# PA_Receiver.net
KiCad netlist of a schematic drawn in Altium Designer
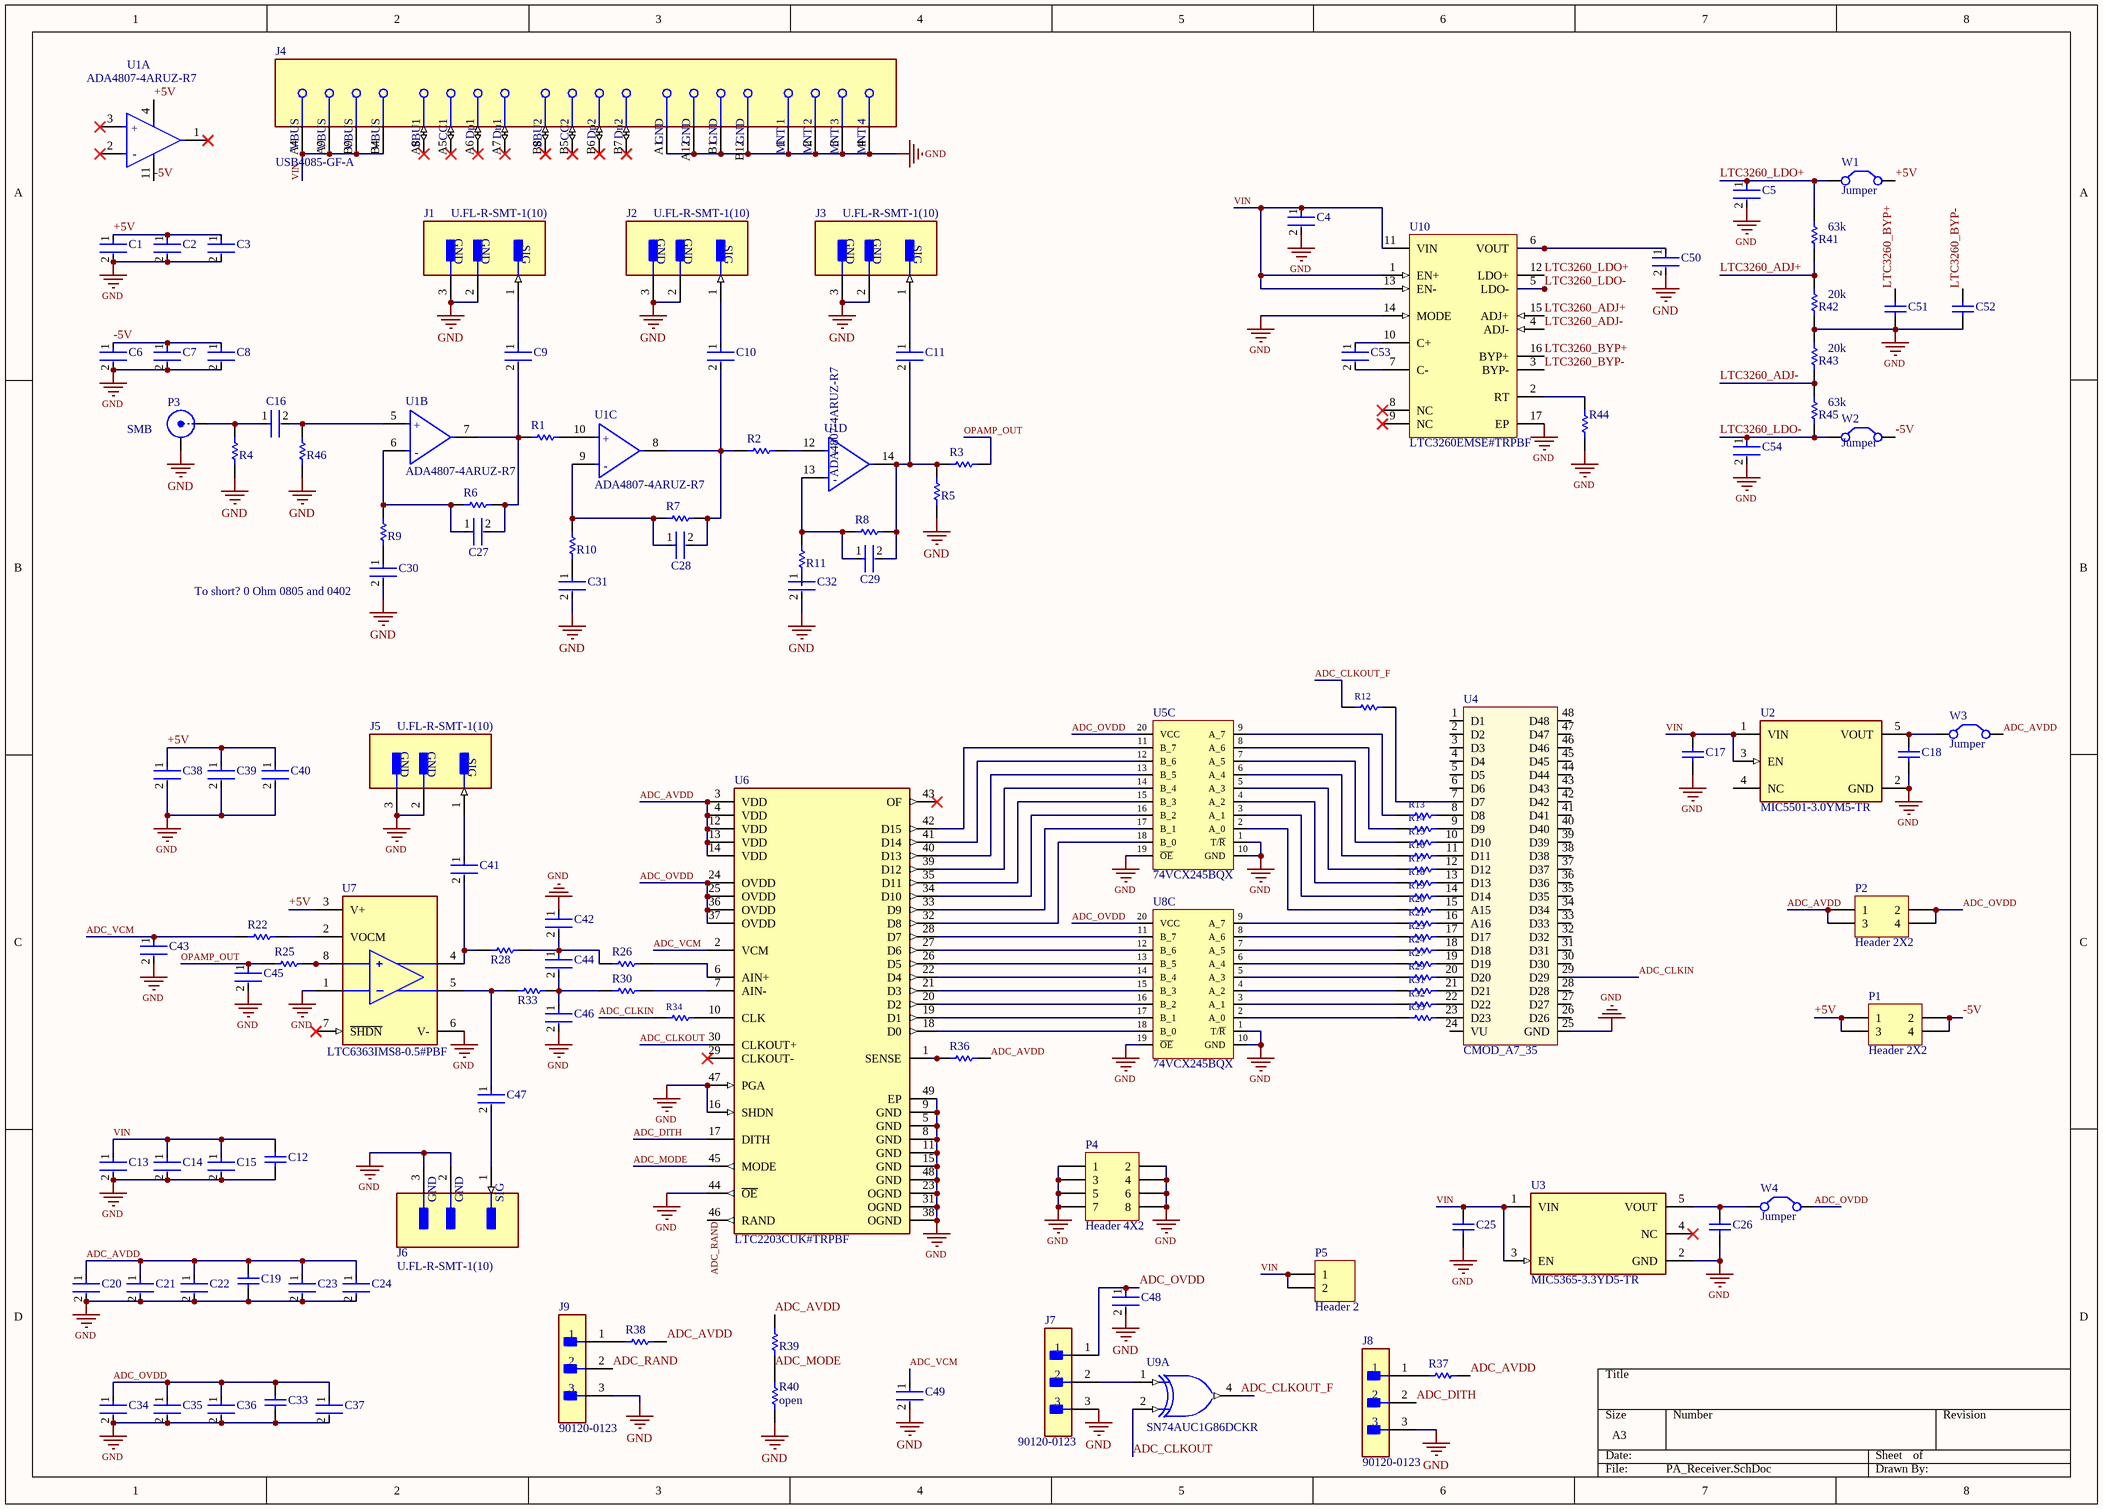
[diagram p0: PA_Receiver.SchDoc]

(export (version "E")
  (design (tool "Eeschema 10.0.6"))
  (components
    (comp (ref "C1")
      (value "CL21B106KOQNNNG")
      (footprint "FP-CL21B106KOQNNNG-MFG")
      (description "CAP CER 10UF 16V X7R 0805")
      (fields
        (field (name "TOLERANCE") "10%")
        (field (name "OCTOPART") "https://octopart.com/cl21b106koqnnng-samsung-19995691")
      )
      (libsource (lib "Altium Content Vault") (part "b4654b650e69147ec39a6b967a45e02"))
    )
    (comp (ref "C2")
      (value "GRM21BR71C475KE51K")
      (footprint "FP-GRM21B-0_15-MFG")
      (description "Chip Multilayer Ceramic Capacitors for General Purpose, 0805, 4.7uF, X7R, 15%, 10%, 16V")
      (fields (field (name "TOLERANCE") "10%"))
      (libsource (lib "Altium Content Vault") (part "b4654b650e69147ec39a6b967a45e02"))
    )
    (comp (ref "C3")
      (value "C0805C104K5RACTU")
      (footprint "FP-C0805C-DN-MFG")
      (description "CAP CER 0.1UF 50V X7R 0805")
      (fields
        (field (name "MANUFACTURER") "KEMET")
        (field (name "OCTOPART") "https://octopart.com/c0805c104k5ractu-kemet-143926")
      )
      (libsource (lib "Altium Content Vault") (part "b4654b650e69147ec39a6b967a45e02"))
    )
    (comp (ref "C4")
      (value "CL21B106KOQNNNG")
      (footprint "FP-CL21B106KOQNNNG-MFG")
      (description "CAP CER 10UF 16V X7R 0805")
      (fields
        (field (name "TOLERANCE") "10%")
        (field (name "OCTOPART") "https://octopart.com/cl21b106koqnnng-samsung-19995691")
      )
      (libsource (lib "Altium Content Vault") (part "b4654b650e69147ec39a6b967a45e02"))
    )
    (comp (ref "C5")
      (value "CL21B106KOQNNNG")
      (footprint "FP-CL21B106KOQNNNG-MFG")
      (description "CAP CER 10UF 16V X7R 0805")
      (fields
        (field (name "TOLERANCE") "10%")
        (field (name "OCTOPART") "https://octopart.com/cl21b106koqnnng-samsung-19995691")
      )
      (libsource (lib "Altium Content Vault") (part "b4654b650e69147ec39a6b967a45e02"))
    )
    (comp (ref "C6")
      (value "CL21B106KOQNNNG")
      (footprint "FP-CL21B106KOQNNNG-MFG")
      (description "CAP CER 10UF 16V X7R 0805")
      (fields
        (field (name "TOLERANCE") "10%")
        (field (name "OCTOPART") "https://octopart.com/cl21b106koqnnng-samsung-19995691")
      )
      (libsource (lib "Altium Content Vault") (part "b4654b650e69147ec39a6b967a45e02"))
    )
    (comp (ref "C7")
      (value "GRM21BR71C475KE51K")
      (footprint "FP-GRM21B-0_15-MFG")
      (description "Chip Multilayer Ceramic Capacitors for General Purpose, 0805, 4.7uF, X7R, 15%, 10%, 16V")
      (fields (field (name "TOLERANCE") "10%"))
      (libsource (lib "Altium Content Vault") (part "b4654b650e69147ec39a6b967a45e02"))
    )
    (comp (ref "C8")
      (value "C0805C104K5RACTU")
      (footprint "FP-C0805C-DN-MFG")
      (description "CAP CER 0.1UF 50V X7R 0805")
      (fields
        (field (name "MANUFACTURER") "KEMET")
        (field (name "OCTOPART") "https://octopart.com/c0805c104k5ractu-kemet-143926")
      )
      (libsource (lib "Altium Content Vault") (part "b4654b650e69147ec39a6b967a45e02"))
    )
    (comp (ref "C9")
      (value "C0805C102K5RACTU")
      (footprint "FP-C0805C-DN-MFG")
      (description "CAP CER 1000PF 50V X7R 0805")
      (fields
        (field (name "OCTOPART") "https://octopart.com/c0805c102k5ractu-kemet-93010")
        (field (name "TOLERANCE") "0.1")
      )
      (libsource (lib "Altium Content Vault") (part "b4654b650e69147ec39a6b967a45e02"))
    )
    (comp (ref "C10")
      (value "C0805C102K5RACTU")
      (footprint "FP-C0805C-DN-MFG")
      (description "CAP CER 1000PF 50V X7R 0805")
      (fields
        (field (name "OCTOPART") "https://octopart.com/c0805c102k5ractu-kemet-93010")
        (field (name "TOLERANCE") "0.1")
      )
      (libsource (lib "Altium Content Vault") (part "b4654b650e69147ec39a6b967a45e02"))
    )
    (comp (ref "C11")
      (value "C0805C102K5RACTU")
      (footprint "FP-C0805C-DN-MFG")
      (description "CAP CER 1000PF 50V X7R 0805")
      (fields
        (field (name "OCTOPART") "https://octopart.com/c0805c102k5ractu-kemet-93010")
        (field (name "TOLERANCE") "0.1")
      )
      (libsource (lib "Altium Content Vault") (part "b4654b650e69147ec39a6b967a45e02"))
    )
    (comp (ref "C12")
      (value "C0805C105K3RACTU")
      (footprint "CAPC2013X140X50LL20T25")
      (fields (field (name "MANUFACTURER") "Kemet"))
      (libsource (lib "Altium Content Vault") (part "CAP"))
    )
    (comp (ref "C13")
      (value "CL21B106KOQNNNG")
      (footprint "FP-CL21B106KOQNNNG-MFG")
      (description "CAP CER 10UF 16V X7R 0805")
      (fields
        (field (name "TOLERANCE") "10%")
        (field (name "OCTOPART") "https://octopart.com/cl21b106koqnnng-samsung-19995691")
      )
      (libsource (lib "Altium Content Vault") (part "b4654b650e69147ec39a6b967a45e02"))
    )
    (comp (ref "C14")
      (value "GRM21BR71C475KE51K")
      (footprint "FP-GRM21B-0_15-MFG")
      (description "Chip Multilayer Ceramic Capacitors for General Purpose, 0805, 4.7uF, X7R, 15%, 10%, 16V")
      (fields (field (name "TOLERANCE") "10%"))
      (libsource (lib "Altium Content Vault") (part "b4654b650e69147ec39a6b967a45e02"))
    )
    (comp (ref "C15")
      (value "C0805C104K5RACTU")
      (footprint "FP-C0805C-DN-MFG")
      (description "CAP CER 0.1UF 50V X7R 0805")
      (fields
        (field (name "MANUFACTURER") "KEMET")
        (field (name "OCTOPART") "https://octopart.com/c0805c104k5ractu-kemet-143926")
      )
      (libsource (lib "Altium Content Vault") (part "b4654b650e69147ec39a6b967a45e02"))
    )
    (comp (ref "C16")
      (value "CL21B222JBANNNC")
      (footprint "FP-CL21-IPC_B")
      (description "CL21 Series 0805 2.2nF 50V ±5% Tolerance X7R Multilayer Ceramic Chip Capacitor")
      (fields (field (name "TOLERANCE") "5%") (field (name "VOLTAGE") "50V"))
      (libsource (lib "Altium Content Vault") (part "b4654b650e69147ec39a6b967a45e02"))
    )
    (comp (ref "C17")
      (value "C0805C105K3RACTU")
      (footprint "CAPC2013X140X50LL20T25")
      (fields (field (name "MANUFACTURER") "Kemet"))
      (libsource (lib "Altium Content Vault") (part "CAP"))
    )
    (comp (ref "C18")
      (value "C0805C105K3RACTU")
      (footprint "CAPC2013X140X50LL20T25")
      (fields (field (name "MANUFACTURER") "Kemet"))
      (libsource (lib "Altium Content Vault") (part "CAP"))
    )
    (comp (ref "C19")
      (value "C0805C105K3RACTU")
      (footprint "CAPC2013X140X50LL20T25")
      (fields (field (name "MANUFACTURER") "Kemet"))
      (libsource (lib "Altium Content Vault") (part "CAP"))
    )
    (comp (ref "C20")
      (value "CL21B106KOQNNNG")
      (footprint "FP-CL21B106KOQNNNG-MFG")
      (description "CAP CER 10UF 16V X7R 0805")
      (fields
        (field (name "TOLERANCE") "10%")
        (field (name "OCTOPART") "https://octopart.com/cl21b106koqnnng-samsung-19995691")
      )
      (libsource (lib "Altium Content Vault") (part "b4654b650e69147ec39a6b967a45e02"))
    )
    (comp (ref "C21")
      (value "GRM21BR71C475KE51K")
      (footprint "FP-GRM21B-0_15-MFG")
      (description "Chip Multilayer Ceramic Capacitors for General Purpose, 0805, 4.7uF, X7R, 15%, 10%, 16V")
      (fields (field (name "TOLERANCE") "10%"))
      (libsource (lib "Altium Content Vault") (part "b4654b650e69147ec39a6b967a45e02"))
    )
    (comp (ref "C22")
      (value "C0805C104K5RACTU")
      (footprint "FP-C0805C-DN-MFG")
      (description "CAP CER 0.1UF 50V X7R 0805")
      (fields
        (field (name "MANUFACTURER") "KEMET")
        (field (name "OCTOPART") "https://octopart.com/c0805c104k5ractu-kemet-143926")
      )
      (libsource (lib "Altium Content Vault") (part "b4654b650e69147ec39a6b967a45e02"))
    )
    (comp (ref "C23")
      (value "C0805C104K5RACTU")
      (footprint "FP-C0805C-DN-MFG")
      (description "CAP CER 0.1UF 50V X7R 0805")
      (fields
        (field (name "MANUFACTURER") "KEMET")
        (field (name "OCTOPART") "https://octopart.com/c0805c104k5ractu-kemet-143926")
      )
      (libsource (lib "Altium Content Vault") (part "b4654b650e69147ec39a6b967a45e02"))
    )
    (comp (ref "C24")
      (value "C0805C104K5RACTU")
      (footprint "FP-C0805C-DN-MFG")
      (description "CAP CER 0.1UF 50V X7R 0805")
      (fields
        (field (name "MANUFACTURER") "KEMET")
        (field (name "OCTOPART") "https://octopart.com/c0805c104k5ractu-kemet-143926")
      )
      (libsource (lib "Altium Content Vault") (part "b4654b650e69147ec39a6b967a45e02"))
    )
    (comp (ref "C25")
      (value "C0805C105K3RACTU")
      (footprint "CAPC2013X140X50LL20T25")
      (fields (field (name "MANUFACTURER") "Kemet"))
      (libsource (lib "Altium Content Vault") (part "CAP"))
    )
    (comp (ref "C26")
      (value "C0805C105K3RACTU")
      (footprint "CAPC2013X140X50LL20T25")
      (fields (field (name "MANUFACTURER") "Kemet"))
      (libsource (lib "Altium Content Vault") (part "CAP"))
    )
    (comp (ref "C27")
      (value "C0805C150K5RACTU")
      (footprint "FP-C0805C-DN-MFG")
      (description "CAP CER SMD 0805 15PF 50V 10% X7")
      (fields
        (field (name "OCTOPART") "https://octopart.com/c0805c150k5ractu-kemet-88373275")
        (field (name "MANUFACTURER") "KEMET")
      )
      (libsource (lib "Altium Content Vault") (part "b4654b650e69147ec39a6b967a45e02"))
    )
    (comp (ref "C28")
      (value "C0805C150K5RACTU")
      (footprint "FP-C0805C-DN-MFG")
      (description "CAP CER SMD 0805 15PF 50V 10% X7")
      (fields
        (field (name "OCTOPART") "https://octopart.com/c0805c150k5ractu-kemet-88373275")
        (field (name "MANUFACTURER") "KEMET")
      )
      (libsource (lib "Altium Content Vault") (part "b4654b650e69147ec39a6b967a45e02"))
    )
    (comp (ref "C29")
      (value "C0805C150K5RACTU")
      (footprint "FP-C0805C-DN-MFG")
      (description "CAP CER SMD 0805 15PF 50V 10% X7")
      (fields
        (field (name "OCTOPART") "https://octopart.com/c0805c150k5ractu-kemet-88373275")
        (field (name "MANUFACTURER") "KEMET")
      )
      (libsource (lib "Altium Content Vault") (part "b4654b650e69147ec39a6b967a45e02"))
    )
    (comp (ref "C30")
      (value "CL21B106KOQNNNG")
      (footprint "FP-CL21B106KOQNNNG-MFG")
      (description "CAP CER 10UF 16V X7R 0805")
      (fields
        (field (name "TOLERANCE") "10%")
        (field (name "OCTOPART") "https://octopart.com/cl21b106koqnnng-samsung-19995691")
      )
      (libsource (lib "Altium Content Vault") (part "b4654b650e69147ec39a6b967a45e02"))
    )
    (comp (ref "C31")
      (value "CL21B106KOQNNNG")
      (footprint "FP-CL21B106KOQNNNG-MFG")
      (description "CAP CER 10UF 16V X7R 0805")
      (fields
        (field (name "TOLERANCE") "10%")
        (field (name "OCTOPART") "https://octopart.com/cl21b106koqnnng-samsung-19995691")
      )
      (libsource (lib "Altium Content Vault") (part "b4654b650e69147ec39a6b967a45e02"))
    )
    (comp (ref "C32")
      (value "CL21B106KOQNNNG")
      (footprint "FP-CL21B106KOQNNNG-MFG")
      (description "CAP CER 10UF 16V X7R 0805")
      (fields
        (field (name "TOLERANCE") "10%")
        (field (name "OCTOPART") "https://octopart.com/cl21b106koqnnng-samsung-19995691")
      )
      (libsource (lib "Altium Content Vault") (part "b4654b650e69147ec39a6b967a45e02"))
    )
    (comp (ref "C33")
      (value "C0805C105K3RACTU")
      (footprint "CAPC2013X140X50LL20T25")
      (fields (field (name "MANUFACTURER") "Kemet"))
      (libsource (lib "Altium Content Vault") (part "CAP"))
    )
    (comp (ref "C34")
      (value "CL21B106KOQNNNG")
      (footprint "FP-CL21B106KOQNNNG-MFG")
      (description "CAP CER 10UF 16V X7R 0805")
      (fields
        (field (name "TOLERANCE") "10%")
        (field (name "OCTOPART") "https://octopart.com/cl21b106koqnnng-samsung-19995691")
      )
      (libsource (lib "Altium Content Vault") (part "b4654b650e69147ec39a6b967a45e02"))
    )
    (comp (ref "C35")
      (value "GRM21BR71C475KE51K")
      (footprint "FP-GRM21B-0_15-MFG")
      (description "Chip Multilayer Ceramic Capacitors for General Purpose, 0805, 4.7uF, X7R, 15%, 10%, 16V")
      (fields (field (name "TOLERANCE") "10%"))
      (libsource (lib "Altium Content Vault") (part "b4654b650e69147ec39a6b967a45e02"))
    )
    (comp (ref "C36")
      (value "C0805C104K5RACTU")
      (footprint "FP-C0805C-DN-MFG")
      (description "CAP CER 0.1UF 50V X7R 0805")
      (fields
        (field (name "MANUFACTURER") "KEMET")
        (field (name "OCTOPART") "https://octopart.com/c0805c104k5ractu-kemet-143926")
      )
      (libsource (lib "Altium Content Vault") (part "b4654b650e69147ec39a6b967a45e02"))
    )
    (comp (ref "C37")
      (value "C0805C104K5RACTU")
      (footprint "FP-C0805C-DN-MFG")
      (description "CAP CER 0.1UF 50V X7R 0805")
      (fields
        (field (name "MANUFACTURER") "KEMET")
        (field (name "OCTOPART") "https://octopart.com/c0805c104k5ractu-kemet-143926")
      )
      (libsource (lib "Altium Content Vault") (part "b4654b650e69147ec39a6b967a45e02"))
    )
    (comp (ref "C38")
      (value "CL21B106KOQNNNG")
      (footprint "FP-CL21B106KOQNNNG-MFG")
      (description "CAP CER 10UF 16V X7R 0805")
      (fields
        (field (name "TOLERANCE") "10%")
        (field (name "OCTOPART") "https://octopart.com/cl21b106koqnnng-samsung-19995691")
      )
      (libsource (lib "Altium Content Vault") (part "b4654b650e69147ec39a6b967a45e02"))
    )
    (comp (ref "C39")
      (value "GRM21BR71C475KE51K")
      (footprint "FP-GRM21B-0_15-MFG")
      (description "Chip Multilayer Ceramic Capacitors for General Purpose, 0805, 4.7uF, X7R, 15%, 10%, 16V")
      (fields (field (name "TOLERANCE") "10%"))
      (libsource (lib "Altium Content Vault") (part "b4654b650e69147ec39a6b967a45e02"))
    )
    (comp (ref "C40")
      (value "C0805C104K5RACTU")
      (footprint "FP-C0805C-DN-MFG")
      (description "CAP CER 0.1UF 50V X7R 0805")
      (fields
        (field (name "MANUFACTURER") "KEMET")
        (field (name "OCTOPART") "https://octopart.com/c0805c104k5ractu-kemet-143926")
      )
      (libsource (lib "Altium Content Vault") (part "b4654b650e69147ec39a6b967a45e02"))
    )
    (comp (ref "C41")
      (value "C0805C102K5RACTU")
      (footprint "FP-C0805C-DN-MFG")
      (description "CAP CER 1000PF 50V X7R 0805")
      (fields
        (field (name "OCTOPART") "https://octopart.com/c0805c102k5ractu-kemet-93010")
        (field (name "TOLERANCE") "0.1")
      )
      (libsource (lib "Altium Content Vault") (part "b4654b650e69147ec39a6b967a45e02"))
    )
    (comp (ref "C42")
      (value "C0805C100J5RACTU")
      (footprint "FP-C0805C-DN-MFG")
      (description "C0805 10 pF X7R 30ppm/°C 5.00% 50 V")
      (fields
        (field (name "OCTOPART") "https://octopart.com/c0805c100j5ractu-kemet-81794931")
        (field (name "MANUFACTURER") "KEMET")
      )
      (libsource (lib "Altium Content Vault") (part "b4654b650e69147ec39a6b967a45e02"))
    )
    (comp (ref "C43")
      (value "C0805C104K5RACTU")
      (footprint "FP-C0805C-DN-MFG")
      (description "CAP CER 0.1UF 50V X7R 0805")
      (fields
        (field (name "MANUFACTURER") "KEMET")
        (field (name "OCTOPART") "https://octopart.com/c0805c104k5ractu-kemet-143926")
      )
      (libsource (lib "Altium Content Vault") (part "b4654b650e69147ec39a6b967a45e02"))
    )
    (comp (ref "C44")
      (value "C0805C100J5RACTU")
      (footprint "FP-C0805C-DN-MFG")
      (description "C0805 10 pF X7R 30ppm/°C 5.00% 50 V")
      (fields
        (field (name "OCTOPART") "https://octopart.com/c0805c100j5ractu-kemet-81794931")
        (field (name "MANUFACTURER") "KEMET")
      )
      (libsource (lib "Altium Content Vault") (part "b4654b650e69147ec39a6b967a45e02"))
    )
    (comp (ref "C45")
      (value "C0805C100J5RACTU")
      (footprint "FP-C0805C-DN-MFG")
      (description "C0805 10 pF X7R 30ppm/°C 5.00% 50 V")
      (fields
        (field (name "OCTOPART") "https://octopart.com/c0805c100j5ractu-kemet-81794931")
        (field (name "MANUFACTURER") "KEMET")
      )
      (libsource (lib "Altium Content Vault") (part "b4654b650e69147ec39a6b967a45e02"))
    )
    (comp (ref "C46")
      (value "C0805C100J5RACTU")
      (footprint "FP-C0805C-DN-MFG")
      (description "C0805 10 pF X7R 30ppm/°C 5.00% 50 V")
      (fields
        (field (name "OCTOPART") "https://octopart.com/c0805c100j5ractu-kemet-81794931")
        (field (name "MANUFACTURER") "KEMET")
      )
      (libsource (lib "Altium Content Vault") (part "b4654b650e69147ec39a6b967a45e02"))
    )
    (comp (ref "C47")
      (value "C0805C102K5RACTU")
      (footprint "FP-C0805C-DN-MFG")
      (description "CAP CER 1000PF 50V X7R 0805")
      (fields
        (field (name "OCTOPART") "https://octopart.com/c0805c102k5ractu-kemet-93010")
        (field (name "TOLERANCE") "0.1")
      )
      (libsource (lib "Altium Content Vault") (part "b4654b650e69147ec39a6b967a45e02"))
    )
    (comp (ref "C48")
      (value "C0805C104K5RACTU")
      (footprint "FP-C0805C-DN-MFG")
      (description "CAP CER 0.1UF 50V X7R 0805")
      (fields
        (field (name "MANUFACTURER") "KEMET")
        (field (name "OCTOPART") "https://octopart.com/c0805c104k5ractu-kemet-143926")
      )
      (libsource (lib "Altium Content Vault") (part "b4654b650e69147ec39a6b967a45e02"))
    )
    (comp (ref "C49")
      (value "C2012X7R1C225K125AB")
      (footprint "FP-C2012-125-0_2-MFG")
      (description "Multilayer Ceramic Capacitors 2.2μF ±10% 16V X7R SMD 0805")
      (fields (field (name "TOLERANCE") "10%") (field (name "VOLTAGE") "16V"))
      (libsource (lib "Altium Content Vault") (part "b4654b650e69147ec39a6b967a45e02"))
    )
    (comp (ref "C50")
      (value "CL21B106KOQNNNG")
      (footprint "FP-CL21B106KOQNNNG-MFG")
      (description "CAP CER 10UF 16V X7R 0805")
      (fields
        (field (name "TOLERANCE") "10%")
        (field (name "OCTOPART") "https://octopart.com/cl21b106koqnnng-samsung-19995691")
      )
      (libsource (lib "Altium Content Vault") (part "b4654b650e69147ec39a6b967a45e02"))
    )
    (comp (ref "C51")
      (value "C0805F103K5RACTU")
      (footprint "CAPC2013X100X50NL20T25")
      (fields (field (name "MANUFACTURER") "Kemet"))
      (libsource (lib "Altium Content Vault") (part "CAP"))
    )
    (comp (ref "C52")
      (value "C0805F103K5RACTU")
      (footprint "CAPC2013X100X50NL20T25")
      (fields (field (name "MANUFACTURER") "Kemet"))
      (libsource (lib "Altium Content Vault") (part "CAP"))
    )
    (comp (ref "C53")
      (value "CL21B105KAFNNNG")
      (footprint "FP-CL21-IPC_C")
      (description "CL21 Series 0805 1uF 25V ±10% Tolerance X7R Multilayer Ceramic Chip Capacitor")
      (fields (field (name "TOLERANCE") "10%") (field (name "VOLTAGE") "25V"))
      (libsource (lib "Altium Content Vault") (part "b4654b650e69147ec39a6b967a45e02"))
    )
    (comp (ref "C54")
      (value "CL21B106KOQNNNG")
      (footprint "FP-CL21B106KOQNNNG-MFG")
      (description "CAP CER 10UF 16V X7R 0805")
      (fields
        (field (name "TOLERANCE") "10%")
        (field (name "OCTOPART") "https://octopart.com/cl21b106koqnnng-samsung-19995691")
      )
      (libsource (lib "Altium Content Vault") (part "b4654b650e69147ec39a6b967a45e02"))
    )
    (comp (ref "J1")
      (value "U.FL-R-SMT-1(10)")
      (footprint "FP-U_FL-R-SMT-1_10-MFG")
      (description "CONN U.FL RCPT STR 50 OHM SMD")
      (libsource (lib "") (part "7158abf7d987fa84906f6fb0d115710_1"))
    )
    (comp (ref "J2")
      (value "U.FL-R-SMT-1(10)")
      (footprint "FP-U_FL-R-SMT-1_10-MFG")
      (description "CONN U.FL RCPT STR 50 OHM SMD")
      (libsource (lib "") (part "7158abf7d987fa84906f6fb0d115710_1"))
    )
    (comp (ref "J3")
      (value "U.FL-R-SMT-1(10)")
      (footprint "FP-U_FL-R-SMT-1_10-MFG")
      (description "CONN U.FL RCPT STR 50 OHM SMD")
      (libsource (lib "") (part "7158abf7d987fa84906f6fb0d115710_1"))
    )
    (comp (ref "J4")
      (value "USB4085-GF-A")
      (footprint "FP-USB4085-GF-A-MFG")
      (description "CONN RCPT USB2.0 TYPE C 24POS RA")
      (libsource (lib "Altium Content Vault") (part "10fa745527c8b974685cbca3c197132"))
    )
    (comp (ref "J5")
      (value "U.FL-R-SMT-1(10)")
      (footprint "FP-U_FL-R-SMT-1_10-MFG")
      (description "CONN U.FL RCPT STR 50 OHM SMD")
      (libsource (lib "") (part "7158abf7d987fa84906f6fb0d115710_1"))
    )
    (comp (ref "J6")
      (value "U.FL-R-SMT-1(10)")
      (footprint "FP-U_FL-R-SMT-1_10-MFG")
      (description "CONN U.FL RCPT STR 50 OHM SMD")
      (libsource (lib "Altium Content Vault") (part "7158abf7d987fa84906f6fb0d115710"))
    )
    (comp (ref "J7")
      (value "90120-0123")
      (footprint "FP-90120-0123-MFG")
      (description "CONN HEADER VERT 3POS 2.54MM")
      (libsource (lib "Altium Content Vault") (part "0d3f023dd272f625e17a2be33dea85f"))
    )
    (comp (ref "J8")
      (value "90120-0123")
      (footprint "FP-90120-0123-MFG")
      (description "CONN HEADER VERT 3POS 2.54MM")
      (libsource (lib "Altium Content Vault") (part "0d3f023dd272f625e17a2be33dea85f"))
    )
    (comp (ref "J9")
      (value "90120-0123")
      (footprint "FP-90120-0123-MFG")
      (description "CONN HEADER VERT 3POS 2.54MM")
      (libsource (lib "Altium Content Vault") (part "0d3f023dd272f625e17a2be33dea85f"))
    )
    (comp (ref "P1")
      (value "Header 2X2")
      (footprint "HDR2X2")
      (description "Header, 2-Pin, Dual row")
      (fields (field (name "PUBLISHER") "Altium Limited"))
      (libsource (lib "Miscellaneous Connectors") (part "Header 2X2"))
    )
    (comp (ref "P2")
      (value "Header 2X2")
      (footprint "HDR2X2")
      (description "Header, 2-Pin, Dual row")
      (fields (field (name "PUBLISHER") "Altium Limited"))
      (libsource (lib "Miscellaneous Connectors") (part "Header 2X2"))
    )
    (comp (ref "P3")
      (value "SMB")
      (footprint "SMB_V-RJ45")
      (description "SMB Straight Connector")
      (fields (field (name "PUBLISHER") "Altium Limited"))
      (libsource (lib "Miscellaneous Connectors") (part "SMB"))
    )
    (comp (ref "P4")
      (value "Header 4X2")
      (footprint "HDR2X4")
      (description "Header, 4-Pin, Dual row")
      (fields (field (name "PUBLISHER") "Altium Limited"))
      (libsource (lib "Miscellaneous Connectors") (part "Header 4X2"))
    )
    (comp (ref "P5")
      (value "Header 2")
      (footprint "HDR1X2")
      (description "Header, 2-Pin")
      (fields (field (name "PUBLISHER") "Altium Limited"))
      (libsource (lib "Miscellaneous Connectors") (part "Header 2"))
    )
    (comp (ref "R1")
      (value "RC0805FR-071KL")
      (footprint "RESC2013X60X35ML10T20")
      (description "Chip Resistor, 1 KOhm, +/- 1%, 125 mW, -55 to 155 degC, 0805 (2012 Metric), RoHS, Tape and Reel")
      (fields (field (name "TOLERANCE") "1%") (field (name "MANUFACTURER") "Yageo"))
      (libsource (lib "Altium Content Vault") (part "RES-2"))
    )
    (comp (ref "R2")
      (value "RC0805FR-071KL")
      (footprint "RESC2013X60X35ML10T20")
      (description "Chip Resistor, 1 KOhm, +/- 1%, 125 mW, -55 to 155 degC, 0805 (2012 Metric), RoHS, Tape and Reel")
      (fields (field (name "TOLERANCE") "1%") (field (name "MANUFACTURER") "Yageo"))
      (libsource (lib "Altium Content Vault") (part "RES-2"))
    )
    (comp (ref "R3")
      (value "ERJ-6GEY0R00V")
      (footprint "RESC2013X70X40NL20T20")
      (description "Chip Resistor, 0 Ohm, +/- 1%, 0.125 W, -55 to 155 degC, 0805 (2012 Metric), RoHS, Tape and Reel")
      (fields (field (name "TOLERANCE") "5%"))
      (libsource (lib "Altium Content Vault") (part "RES-2"))
    )
    (comp (ref "R4")
      (value "RK73B2ATTD510J")
      (footprint "RESC2013X60X30ML20T20")
      (fields (field (name "MANUFACTURER") "KOA Speer"))
      (libsource (lib "Altium Content Vault") (part "RES"))
    )
    (comp (ref "R5")
      (value "RK73B2ATTD510J")
      (footprint "RESC2013X60X30ML20T20")
      (fields (field (name "MANUFACTURER") "KOA Speer"))
      (libsource (lib "Altium Content Vault") (part "RES"))
    )
    (comp (ref "R6")
      (value "RC0805FR-071KL")
      (footprint "RESC2013X60X35ML10T20")
      (description "Chip Resistor, 1 KOhm, +/- 1%, 125 mW, -55 to 155 degC, 0805 (2012 Metric), RoHS, Tape and Reel")
      (fields (field (name "TOLERANCE") "1%") (field (name "MANUFACTURER") "Yageo"))
      (libsource (lib "Altium Content Vault") (part "RES-2"))
    )
    (comp (ref "R7")
      (value "RC0805FR-071KL")
      (footprint "RESC2013X60X35ML10T20")
      (description "Chip Resistor, 1 KOhm, +/- 1%, 125 mW, -55 to 155 degC, 0805 (2012 Metric), RoHS, Tape and Reel")
      (fields (field (name "TOLERANCE") "1%") (field (name "MANUFACTURER") "Yageo"))
      (libsource (lib "Altium Content Vault") (part "RES-2"))
    )
    (comp (ref "R8")
      (value "RC0805FR-071KL")
      (footprint "RESC2013X60X35ML10T20")
      (description "Chip Resistor, 1 KOhm, +/- 1%, 125 mW, -55 to 155 degC, 0805 (2012 Metric), RoHS, Tape and Reel")
      (fields (field (name "TOLERANCE") "1%") (field (name "MANUFACTURER") "Yageo"))
      (libsource (lib "Altium Content Vault") (part "RES-2"))
    )
    (comp (ref "R9")
      (value "RC0805FR-07100RL")
      (footprint "RESC2013X60X35ML10T20")
      (description "Chip Resistor, 100 Ohm, +/-1%, 0.125 W, -55 to 155 degC, 0805 (2012 Metric), RoHS, Tape and Reel")
      (fields (field (name "TOLERANCE") "1%") (field (name "MANUFACTURER") "Yageo"))
      (libsource (lib "Altium Content Vault") (part "RES-2"))
    )
    (comp (ref "R10")
      (value "RC0805FR-07100RL")
      (footprint "RESC2013X60X35ML10T20")
      (description "Chip Resistor, 100 Ohm, +/-1%, 0.125 W, -55 to 155 degC, 0805 (2012 Metric), RoHS, Tape and Reel")
      (fields (field (name "TOLERANCE") "1%") (field (name "MANUFACTURER") "Yageo"))
      (libsource (lib "Altium Content Vault") (part "RES-2"))
    )
    (comp (ref "R11")
      (value "RC0805FR-07100RL")
      (footprint "RESC2013X60X35ML10T20")
      (description "Chip Resistor, 100 Ohm, +/-1%, 0.125 W, -55 to 155 degC, 0805 (2012 Metric), RoHS, Tape and Reel")
      (fields (field (name "TOLERANCE") "1%") (field (name "MANUFACTURER") "Yageo"))
      (libsource (lib "Altium Content Vault") (part "RES-2"))
    )
    (comp (ref "R12")
      (value "RC0805FR-0733RL")
      (footprint "RESC2013X60X35LL10T20")
      (description "Chip Resistor, 33 Ohm, +/- 1%, 0.125 W, -55 to 155 degC, 0805 (2012 Metric), RoHS, Tape and Reel")
      (fields (field (name "MANUFACTURER") "Yageo"))
      (libsource (lib "Altium Content Vault") (part "RES-2"))
    )
    (comp (ref "R13")
      (value "RC0805FR-0733RL")
      (footprint "RESC2013X60X35LL10T20")
      (description "Chip Resistor, 33 Ohm, +/- 1%, 0.125 W, -55 to 155 degC, 0805 (2012 Metric), RoHS, Tape and Reel")
      (fields (field (name "MANUFACTURER") "Yageo"))
      (libsource (lib "Altium Content Vault") (part "RES-2"))
    )
    (comp (ref "R14")
      (value "RC0805FR-0733RL")
      (footprint "RESC2013X60X35LL10T20")
      (description "Chip Resistor, 33 Ohm, +/- 1%, 0.125 W, -55 to 155 degC, 0805 (2012 Metric), RoHS, Tape and Reel")
      (fields (field (name "MANUFACTURER") "Yageo"))
      (libsource (lib "Altium Content Vault") (part "RES-2"))
    )
    (comp (ref "R15")
      (value "RC0805FR-0733RL")
      (footprint "RESC2013X60X35LL10T20")
      (description "Chip Resistor, 33 Ohm, +/- 1%, 0.125 W, -55 to 155 degC, 0805 (2012 Metric), RoHS, Tape and Reel")
      (fields (field (name "MANUFACTURER") "Yageo"))
      (libsource (lib "Altium Content Vault") (part "RES-2"))
    )
    (comp (ref "R16")
      (value "RC0805FR-0733RL")
      (footprint "RESC2013X60X35LL10T20")
      (description "Chip Resistor, 33 Ohm, +/- 1%, 0.125 W, -55 to 155 degC, 0805 (2012 Metric), RoHS, Tape and Reel")
      (fields (field (name "MANUFACTURER") "Yageo"))
      (libsource (lib "Altium Content Vault") (part "RES-2"))
    )
    (comp (ref "R17")
      (value "RC0805FR-0733RL")
      (footprint "RESC2013X60X35LL10T20")
      (description "Chip Resistor, 33 Ohm, +/- 1%, 0.125 W, -55 to 155 degC, 0805 (2012 Metric), RoHS, Tape and Reel")
      (fields (field (name "MANUFACTURER") "Yageo"))
      (libsource (lib "Altium Content Vault") (part "RES-2"))
    )
    (comp (ref "R18")
      (value "RC0805FR-0733RL")
      (footprint "RESC2013X60X35LL10T20")
      (description "Chip Resistor, 33 Ohm, +/- 1%, 0.125 W, -55 to 155 degC, 0805 (2012 Metric), RoHS, Tape and Reel")
      (fields (field (name "MANUFACTURER") "Yageo"))
      (libsource (lib "Altium Content Vault") (part "RES-2"))
    )
    (comp (ref "R19")
      (value "RC0805FR-0733RL")
      (footprint "RESC2013X60X35LL10T20")
      (description "Chip Resistor, 33 Ohm, +/- 1%, 0.125 W, -55 to 155 degC, 0805 (2012 Metric), RoHS, Tape and Reel")
      (fields (field (name "MANUFACTURER") "Yageo"))
      (libsource (lib "Altium Content Vault") (part "RES-2"))
    )
    (comp (ref "R20")
      (value "RC0805FR-0733RL")
      (footprint "RESC2013X60X35LL10T20")
      (description "Chip Resistor, 33 Ohm, +/- 1%, 0.125 W, -55 to 155 degC, 0805 (2012 Metric), RoHS, Tape and Reel")
      (fields (field (name "MANUFACTURER") "Yageo"))
      (libsource (lib "Altium Content Vault") (part "RES-2"))
    )
    (comp (ref "R21")
      (value "RC0805FR-0733RL")
      (footprint "RESC2013X60X35LL10T20")
      (description "Chip Resistor, 33 Ohm, +/- 1%, 0.125 W, -55 to 155 degC, 0805 (2012 Metric), RoHS, Tape and Reel")
      (fields (field (name "MANUFACTURER") "Yageo"))
      (libsource (lib "Altium Content Vault") (part "RES-2"))
    )
    (comp (ref "R22")
      (value "RC0805FR-07100RL")
      (footprint "RESC2013X60X35ML10T20")
      (description "Chip Resistor, 100 Ohm, +/-1%, 0.125 W, -55 to 155 degC, 0805 (2012 Metric), RoHS, Tape and Reel")
      (fields (field (name "TOLERANCE") "1%") (field (name "MANUFACTURER") "Yageo"))
      (libsource (lib "Altium Content Vault") (part "RES-2"))
    )
    (comp (ref "R23")
      (value "RC0805FR-0733RL")
      (footprint "RESC2013X60X35LL10T20")
      (description "Chip Resistor, 33 Ohm, +/- 1%, 0.125 W, -55 to 155 degC, 0805 (2012 Metric), RoHS, Tape and Reel")
      (fields (field (name "MANUFACTURER") "Yageo"))
      (libsource (lib "Altium Content Vault") (part "RES-2"))
    )
    (comp (ref "R24")
      (value "RC0805FR-0733RL")
      (footprint "RESC2013X60X35LL10T20")
      (description "Chip Resistor, 33 Ohm, +/- 1%, 0.125 W, -55 to 155 degC, 0805 (2012 Metric), RoHS, Tape and Reel")
      (fields (field (name "MANUFACTURER") "Yageo"))
      (libsource (lib "Altium Content Vault") (part "RES-2"))
    )
    (comp (ref "R25")
      (value "ERJ-6GEY0R00V")
      (footprint "RESC2013X70X40NL20T20")
      (description "Chip Resistor, 0 Ohm, +/- 1%, 0.125 W, -55 to 155 degC, 0805 (2012 Metric), RoHS, Tape and Reel")
      (fields (field (name "TOLERANCE") "5%"))
      (libsource (lib "Altium Content Vault") (part "RES-2"))
    )
    (comp (ref "R26")
      (value "RC0805JR-075R1L")
      (footprint "RESC2013X60X35LL10T20")
      (fields (field (name "MANUFACTURER") "Yageo"))
      (libsource (lib "Altium Content Vault") (part "RES"))
    )
    (comp (ref "R27")
      (value "RC0805FR-0733RL")
      (footprint "RESC2013X60X35LL10T20")
      (description "Chip Resistor, 33 Ohm, +/- 1%, 0.125 W, -55 to 155 degC, 0805 (2012 Metric), RoHS, Tape and Reel")
      (fields (field (name "MANUFACTURER") "Yageo"))
      (libsource (lib "Altium Content Vault") (part "RES-2"))
    )
    (comp (ref "R28")
      (value "RK73B2ATTD510J")
      (footprint "RESC2013X60X30ML20T20")
      (fields (field (name "MANUFACTURER") "KOA Speer"))
      (libsource (lib "Altium Content Vault") (part "RES"))
    )
    (comp (ref "R29")
      (value "RC0805FR-0733RL")
      (footprint "RESC2013X60X35LL10T20")
      (description "Chip Resistor, 33 Ohm, +/- 1%, 0.125 W, -55 to 155 degC, 0805 (2012 Metric), RoHS, Tape and Reel")
      (fields (field (name "MANUFACTURER") "Yageo"))
      (libsource (lib "Altium Content Vault") (part "RES-2"))
    )
    (comp (ref "R30")
      (value "RC0805JR-075R1L")
      (footprint "RESC2013X60X35LL10T20")
      (fields (field (name "MANUFACTURER") "Yageo"))
      (libsource (lib "Altium Content Vault") (part "RES"))
    )
    (comp (ref "R31")
      (value "RC0805FR-0733RL")
      (footprint "RESC2013X60X35LL10T20")
      (description "Chip Resistor, 33 Ohm, +/- 1%, 0.125 W, -55 to 155 degC, 0805 (2012 Metric), RoHS, Tape and Reel")
      (fields (field (name "MANUFACTURER") "Yageo"))
      (libsource (lib "Altium Content Vault") (part "RES-2"))
    )
    (comp (ref "R32")
      (value "RC0805FR-0733RL")
      (footprint "RESC2013X60X35LL10T20")
      (description "Chip Resistor, 33 Ohm, +/- 1%, 0.125 W, -55 to 155 degC, 0805 (2012 Metric), RoHS, Tape and Reel")
      (fields (field (name "MANUFACTURER") "Yageo"))
      (libsource (lib "Altium Content Vault") (part "RES-2"))
    )
    (comp (ref "R33")
      (value "RK73B2ATTD510J")
      (footprint "RESC2013X60X30ML20T20")
      (fields (field (name "MANUFACTURER") "KOA Speer"))
      (libsource (lib "Altium Content Vault") (part "RES"))
    )
    (comp (ref "R34")
      (value "RC0805FR-0733RL")
      (footprint "RESC2013X60X35LL10T20")
      (description "Chip Resistor, 33 Ohm, +/- 1%, 0.125 W, -55 to 155 degC, 0805 (2012 Metric), RoHS, Tape and Reel")
      (fields (field (name "MANUFACTURER") "Yageo"))
      (libsource (lib "Altium Content Vault") (part "RES-2"))
    )
    (comp (ref "R35")
      (value "RC0805FR-0733RL")
      (footprint "RESC2013X60X35LL10T20")
      (description "Chip Resistor, 33 Ohm, +/- 1%, 0.125 W, -55 to 155 degC, 0805 (2012 Metric), RoHS, Tape and Reel")
      (fields (field (name "MANUFACTURER") "Yageo"))
      (libsource (lib "Altium Content Vault") (part "RES-2"))
    )
    (comp (ref "R36")
      (value "RK73H2ATTD10R0F")
      (footprint "RESC2013X60X30ML20T20")
      (fields (field (name "MANUFACTURER") "KOA Speer"))
      (libsource (lib "Altium Content Vault") (part "RES"))
    )
    (comp (ref "R37")
      (value "RK73H2ATTD1002F")
      (footprint "RESC2013X60X30LL20T20")
      (fields (field (name "MANUFACTURER") "KOA Speer"))
      (libsource (lib "Altium Content Vault") (part "RES"))
    )
    (comp (ref "R38")
      (value "RK73H2ATTD1002F")
      (footprint "RESC2013X60X30LL20T20")
      (fields (field (name "MANUFACTURER") "KOA Speer"))
      (libsource (lib "Altium Content Vault") (part "RES"))
    )
    (comp (ref "R39")
      (value "RC0805FR-071KL")
      (footprint "RESC2013X60X35ML10T20")
      (description "Chip Resistor, 1 KOhm, +/- 1%, 125 mW, -55 to 155 degC, 0805 (2012 Metric), RoHS, Tape and Reel")
      (fields (field (name "TOLERANCE") "1%") (field (name "MANUFACTURER") "Yageo"))
      (libsource (lib "Altium Content Vault") (part "RES-2"))
    )
    (comp (ref "R40")
      (value "open")
      (footprint "RESC2013X60X35LL10T20")
      (description "Resistor")
      (libsource (lib "Simulation Generic Components") (part "Resistor"))
    )
    (comp (ref "R41")
      (value "63k")
      (footprint "RESC2013X60X30ML20T20")
      (fields (field (name "PART NUMBER") "RK73B2ATTD510J") (field (name "MANUFACTURER") "KOA Speer"))
      (libsource (lib "Altium Content Vault") (part "RES"))
    )
    (comp (ref "R42")
      (value "20k")
      (footprint "RESC2013X60X30ML20T20")
      (fields (field (name "PART NUMBER") "RK73B2ATTD510J") (field (name "MANUFACTURER") "KOA Speer"))
      (libsource (lib "Altium Content Vault") (part "RES"))
    )
    (comp (ref "R43")
      (value "20k")
      (footprint "RESC2013X60X30ML20T20")
      (fields (field (name "PART NUMBER") "RK73B2ATTD510J") (field (name "MANUFACTURER") "KOA Speer"))
      (libsource (lib "Altium Content Vault") (part "RES"))
    )
    (comp (ref "R44")
      (value "CRCW0805200KFKEA")
      (footprint "RESC2013X50X30NL20T20")
      (fields (field (name "MANUFACTURER") "Vishay Dale"))
      (libsource (lib "Altium Content Vault") (part "RES"))
    )
    (comp (ref "R45")
      (value "63k")
      (footprint "RESC2013X60X30ML20T20")
      (fields (field (name "PART NUMBER") "RK73B2ATTD510J") (field (name "MANUFACTURER") "KOA Speer"))
      (libsource (lib "Altium Content Vault") (part "RES"))
    )
    (comp (ref "R46")
      (value "RK73B2ATTD510J")
      (footprint "RESC2013X60X30ML20T20")
      (fields (field (name "MANUFACTURER") "KOA Speer"))
      (libsource (lib "Altium Content Vault") (part "RES"))
    )
    (comp (ref "U1")
      (value "ADA4807-4ARUZ-R7")
      (footprint "FP-RU-14-IPC_B")
      (description "IC OPAMP VFB 4 CIRCUIT 14TSSOP")
      (libsource (lib "Altium Content Vault") (part "50bd8b37c8612bc519e28063e0f4054"))
    )
    (comp (ref "U2")
      (value "MIC5501-3.0YM5-TR")
      (footprint "FP-SOT23-5LD-PL-1-MFG")
      (description "IC REG LINEAR 3V 300MA SOT23-5")
      (libsource (lib "Altium Content Vault") (part "49efecb8457b62bbb278fcbf558b656"))
    )
    (comp (ref "U3")
      (value "MIC5365-3.3YD5-TR")
      (footprint "FP-TSOT-5LD-PL-1-IPC_C")
      (description "IC REG LIN 3.3V 150MA TSOT23-5")
      (libsource (lib "Altium Content Vault") (part "9cd1ec1f75c858dde3b53bd37fde33b"))
    )
    (comp (ref "U4")
      (value "CMOD_A7_35")
      (footprint "PCBComponent_1")
      (libsource (lib "CMOD_A7_35") (part "CMOD_A7_35"))
    )
    (comp (ref "U5")
      (value "74VCX245BQX")
      (footprint "QFN21P50_450X250X80L40X24T305X105N")
      (description "IC TXRX NON-INVERT 3.6V 20-DQFN")
      (libsource (lib "74VCX245BQX") (part "74VCX245BQX"))
    )
    (comp (ref "U6")
      (value "LTC2203CUK#TRPBF")
      (footprint "FP-UK-48-05-08-1704-IPC_C")
      (description "IC ADC 16BIT PIPELINED 48QFN")
      (libsource (lib "Altium Content Vault") (part "dbb119f1cd0a03bf6852efc88f5839a"))
    )
    (comp (ref "U7")
      (value "LTC6363IMS8-0.5#PBF")
      (footprint "FP-MS8-8-05-08-1660-IPC_A")
      (description "IC OPAMP DIFF 1 CIRCUIT 8MSOP")
      (libsource (lib "Altium Content Vault") (part "10715e18a46888876e82d6eaefdc557"))
    )
    (comp (ref "U8")
      (value "74VCX245BQX")
      (footprint "QFN21P50_450X250X80L40X24T305X105N")
      (description "IC TXRX NON-INVERT 3.6V 20-DQFN")
      (libsource (lib "74VCX245BQX") (part "74VCX245BQX"))
    )
    (comp (ref "U9")
      (value "SN74AUC1G86DCKR")
      (footprint "DCK0005A_N")
      (description "Single 2-Input Exclusive-OR Gate, DCK0005A, LARGE T&R")
      (fields
        (field (name "MANUFACTURER") "Texas Instruments")
        (field (name "GENERIC PART NUMBER") "SN74AUC1G86")
      )
      (libsource (lib "Altium Content Vault") (part "TI-XOR-1-2IN-5"))
    )
    (comp (ref "U10")
      (value "LTC3260EMSE#TRPBF")
      (footprint "LT-MSE-16-EDP_L")
      (fields (field (name "MANUFACTURER") "Linear Technology"))
      (libsource (lib "Altium Content Vault") (part "LT-LTC3260-MSE-16"))
    )
    (comp (ref "W1")
      (value "Jumper")
      (footprint "FP-M20-9990246-MFG")
      (description "Jumper Wire")
      (fields (field (name "PUBLISHER") "Altium Limited"))
      (libsource (lib "Miscellaneous Devices") (part "Jumper"))
    )
    (comp (ref "W2")
      (value "Jumper")
      (footprint "FP-M20-9990246-MFG")
      (description "Jumper Wire")
      (fields (field (name "PUBLISHER") "Altium Limited"))
      (libsource (lib "Miscellaneous Devices") (part "Jumper"))
    )
    (comp (ref "W3")
      (value "Jumper")
      (footprint "FP-M20-9990246-MFG")
      (description "Jumper Wire")
      (fields (field (name "PUBLISHER") "Altium Limited"))
      (libsource (lib "Miscellaneous Devices") (part "Jumper"))
    )
    (comp (ref "W4")
      (value "Jumper")
      (footprint "FP-M20-9990246-MFG")
      (description "Jumper Wire")
      (fields (field (name "PUBLISHER") "Altium Limited"))
      (libsource (lib "Miscellaneous Devices") (part "Jumper"))
    )
  )
  (nets
    (net (code "1") (name "/+5V") (class "Default")
      (node (ref "C1") (pin "1") (pinfunction "1_1") (pintype "passive"))
      (node (ref "C2") (pin "1") (pinfunction "1_1") (pintype "passive"))
      (node (ref "C3") (pin "1") (pinfunction "1_1") (pintype "passive"))
      (node (ref "C38") (pin "1") (pinfunction "1_1") (pintype "passive"))
      (node (ref "C39") (pin "1") (pinfunction "1_1") (pintype "passive"))
      (node (ref "C40") (pin "1") (pinfunction "1_1") (pintype "passive"))
      (node (ref "P1") (pin "1") (pinfunction "1_1") (pintype "passive"))
      (node (ref "P1") (pin "3") (pinfunction "3_3") (pintype "passive"))
      (node (ref "U1") (pin "4") (pinfunction "+VS_4") (pintype "power_in"))
      (node (ref "U7") (pin "3") (pinfunction "V+_3") (pintype "power_in"))
      (node (ref "W1") (pin "2") (pinfunction "C2_2") (pintype "passive"))
    )
    (net (code "2") (name "/-5V") (class "Default")
      (node (ref "C6") (pin "1") (pinfunction "1_1") (pintype "passive"))
      (node (ref "C7") (pin "1") (pinfunction "1_1") (pintype "passive"))
      (node (ref "C8") (pin "1") (pinfunction "1_1") (pintype "passive"))
      (node (ref "P1") (pin "2") (pinfunction "2_2") (pintype "passive"))
      (node (ref "P1") (pin "4") (pinfunction "4_4") (pintype "passive"))
      (node (ref "U1") (pin "11") (pinfunction "-VS_11") (pintype "power_in"))
      (node (ref "W2") (pin "2") (pinfunction "C2_2") (pintype "passive"))
    )
    (net (code "3") (name "/ADC_AVDD") (class "Default")
      (node (ref "C19") (pin "2") (pinfunction "2_2") (pintype "passive"))
      (node (ref "C20") (pin "1") (pinfunction "1_1") (pintype "passive"))
      (node (ref "C21") (pin "1") (pinfunction "1_1") (pintype "passive"))
      (node (ref "C22") (pin "1") (pinfunction "1_1") (pintype "passive"))
      (node (ref "C23") (pin "1") (pinfunction "1_1") (pintype "passive"))
      (node (ref "C24") (pin "1") (pinfunction "1_1") (pintype "passive"))
      (node (ref "P2") (pin "1") (pinfunction "1_1") (pintype "passive"))
      (node (ref "P2") (pin "3") (pinfunction "3_3") (pintype "passive"))
      (node (ref "R36") (pin "2") (pinfunction "2_2") (pintype "passive"))
      (node (ref "R37") (pin "2") (pinfunction "2_2") (pintype "passive"))
      (node (ref "R38") (pin "2") (pinfunction "2_2") (pintype "passive"))
      (node (ref "R39") (pin "2") (pinfunction "2_2") (pintype "passive"))
      (node (ref "U6") (pin "12") (pinfunction "VDD_12") (pintype "power_in"))
      (node (ref "U6") (pin "13") (pinfunction "VDD_13") (pintype "power_in"))
      (node (ref "U6") (pin "14") (pinfunction "VDD_14") (pintype "power_in"))
      (node (ref "U6") (pin "3") (pinfunction "VDD_3") (pintype "power_in"))
      (node (ref "U6") (pin "4") (pinfunction "VDD_4") (pintype "power_in"))
      (node (ref "W3") (pin "2") (pinfunction "C2_2") (pintype "passive"))
    )
    (net (code "4") (name "/ADC_CLKIN") (class "Default")
      (node (ref "R34") (pin "1") (pinfunction "1_1") (pintype "passive"))
      (node (ref "U4") (pin "29") (pinfunction "D29_29") (pintype "passive"))
    )
    (net (code "5") (name "/ADC_CLKOUT") (class "Default")
      (node (ref "U6") (pin "30") (pinfunction "CLKOUT+_30") (pintype "passive"))
      (node (ref "U9") (pin "2") (pinfunction "B_2") (pintype "input"))
    )
    (net (code "6") (name "/ADC_CLKOUT_F") (class "Default")
      (node (ref "R12") (pin "1") (pinfunction "1_1") (pintype "passive"))
      (node (ref "U9") (pin "4") (pinfunction "Y_4") (pintype "output"))
    )
    (net (code "7") (name "/ADC_DITH") (class "Default")
      (node (ref "J8") (pin "2") (pinfunction "2_2") (pintype "passive"))
      (node (ref "U6") (pin "17") (pinfunction "DITH_17") (pintype "passive"))
    )
    (net (code "8") (name "/ADC_MODE") (class "Default")
      (node (ref "R39") (pin "1") (pinfunction "1_1") (pintype "passive"))
      (node (ref "R40") (pin "2") (pinfunction "2_2") (pintype "passive"))
      (node (ref "U6") (pin "45") (pinfunction "MODE_45") (pintype "output"))
    )
    (net (code "9") (name "/ADC_OVDD") (class "Default")
      (node (ref "C33") (pin "2") (pinfunction "2_2") (pintype "passive"))
      (node (ref "C34") (pin "1") (pinfunction "1_1") (pintype "passive"))
      (node (ref "C35") (pin "1") (pinfunction "1_1") (pintype "passive"))
      (node (ref "C36") (pin "1") (pinfunction "1_1") (pintype "passive"))
      (node (ref "C37") (pin "1") (pinfunction "1_1") (pintype "passive"))
      (node (ref "C48") (pin "1") (pinfunction "1_1") (pintype "passive"))
      (node (ref "J7") (pin "1") (pinfunction "1_1") (pintype "passive"))
      (node (ref "P2") (pin "2") (pinfunction "2_2") (pintype "passive"))
      (node (ref "P2") (pin "4") (pinfunction "4_4") (pintype "passive"))
      (node (ref "U5") (pin "20") (pinfunction "VCC_20") (pintype "passive"))
      (node (ref "U6") (pin "24") (pinfunction "OVDD_24") (pintype "power_in"))
      (node (ref "U6") (pin "25") (pinfunction "OVDD_25") (pintype "power_in"))
      (node (ref "U6") (pin "36") (pinfunction "OVDD_36") (pintype "power_in"))
      (node (ref "U6") (pin "37") (pinfunction "OVDD_37") (pintype "power_in"))
      (node (ref "U8") (pin "20") (pinfunction "VCC_20") (pintype "passive"))
      (node (ref "W4") (pin "2") (pinfunction "C2_2") (pintype "passive"))
    )
    (net (code "10") (name "/ADC_RAND") (class "Default")
      (node (ref "J9") (pin "2") (pinfunction "2_2") (pintype "passive"))
      (node (ref "U6") (pin "46") (pinfunction "RAND_46") (pintype "output"))
    )
    (net (code "11") (name "/ADC_VCM") (class "Default")
      (node (ref "C43") (pin "1") (pinfunction "1_1") (pintype "passive"))
      (node (ref "C49") (pin "1") (pinfunction "1_1") (pintype "passive"))
      (node (ref "R22") (pin "1") (pinfunction "1_1") (pintype "passive"))
      (node (ref "U6") (pin "2") (pinfunction "VCM_2") (pintype "passive"))
    )
    (net (code "12") (name "/LTC3260_ADJ+") (class "Default")
      (node (ref "R41") (pin "1") (pinfunction "1_1") (pintype "passive"))
      (node (ref "R42") (pin "2") (pinfunction "2_2") (pintype "passive"))
      (node (ref "U10") (pin "15") (pinfunction "ADJ+_15") (pintype "input"))
    )
    (net (code "13") (name "/LTC3260_ADJ-") (class "Default")
      (node (ref "R43") (pin "1") (pinfunction "1_1") (pintype "passive"))
      (node (ref "R45") (pin "2") (pinfunction "2_2") (pintype "passive"))
      (node (ref "U10") (pin "4") (pinfunction "ADJ-_4") (pintype "input"))
    )
    (net (code "14") (name "/LTC3260_BYP+") (class "Default")
      (node (ref "C51") (pin "2") (pinfunction "2_2") (pintype "passive"))
      (node (ref "U10") (pin "16") (pinfunction "BYP+_16") (pintype "passive"))
    )
    (net (code "15") (name "/LTC3260_BYP-") (class "Default")
      (node (ref "C52") (pin "2") (pinfunction "2_2") (pintype "passive"))
      (node (ref "U10") (pin "3") (pinfunction "BYP-_3") (pintype "passive"))
    )
    (net (code "16") (name "/LTC3260_LDO+") (class "Default")
      (node (ref "C5") (pin "1") (pinfunction "1_1") (pintype "passive"))
      (node (ref "R41") (pin "2") (pinfunction "2_2") (pintype "passive"))
      (node (ref "U10") (pin "12") (pinfunction "LDO+_12") (pintype "power_in"))
      (node (ref "W1") (pin "1") (pinfunction "C1_1") (pintype "passive"))
    )
    (net (code "17") (name "/LTC3260_LDO-") (class "Default")
      (node (ref "C54") (pin "1") (pinfunction "1_1") (pintype "passive"))
      (node (ref "R45") (pin "1") (pinfunction "1_1") (pintype "passive"))
      (node (ref "U10") (pin "5") (pinfunction "LDO-_5") (pintype "power_in"))
      (node (ref "W2") (pin "1") (pinfunction "C1_1") (pintype "passive"))
    )
    (net (code "18") (name "/OPAMP_OUT") (class "Default")
      (node (ref "C45") (pin "1") (pinfunction "1_1") (pintype "passive"))
      (node (ref "R25") (pin "1") (pinfunction "1_1") (pintype "passive"))
      (node (ref "R3") (pin "2") (pinfunction "2_2") (pintype "passive"))
    )
    (net (code "19") (name "/VIN") (class "Default")
      (node (ref "C12") (pin "2") (pinfunction "2_2") (pintype "passive"))
      (node (ref "C13") (pin "1") (pinfunction "1_1") (pintype "passive"))
      (node (ref "C14") (pin "1") (pinfunction "1_1") (pintype "passive"))
      (node (ref "C15") (pin "1") (pinfunction "1_1") (pintype "passive"))
      (node (ref "C17") (pin "2") (pinfunction "2_2") (pintype "passive"))
      (node (ref "C25") (pin "2") (pinfunction "2_2") (pintype "passive"))
      (node (ref "C4") (pin "1") (pinfunction "1_1") (pintype "passive"))
      (node (ref "J4") (pin "A4") (pinfunction "VBUS_A4") (pintype "power_in"))
      (node (ref "J4") (pin "A9") (pinfunction "VBUS_A9") (pintype "power_in"))
      (node (ref "J4") (pin "B4") (pinfunction "VBUS_B4") (pintype "power_in"))
      (node (ref "J4") (pin "B9") (pinfunction "VBUS_B9") (pintype "power_in"))
      (node (ref "P5") (pin "1") (pinfunction "1_1") (pintype "passive"))
      (node (ref "P5") (pin "2") (pinfunction "2_2") (pintype "passive"))
      (node (ref "U10") (pin "1") (pinfunction "EN+_1") (pintype "input"))
      (node (ref "U10") (pin "11") (pinfunction "VIN_11") (pintype "power_in"))
      (node (ref "U10") (pin "13") (pinfunction "EN-_13") (pintype "input"))
      (node (ref "U2") (pin "1") (pinfunction "VIN_1") (pintype "power_in"))
      (node (ref "U2") (pin "3") (pinfunction "EN_3") (pintype "input"))
      (node (ref "U3") (pin "1") (pinfunction "VIN_1") (pintype "power_in"))
      (node (ref "U3") (pin "3") (pinfunction "EN_3") (pintype "input"))
    )
    (net (code "20") (name "GND") (class "Default")
      (node (ref "C1") (pin "2") (pinfunction "2_2") (pintype "passive"))
      (node (ref "C12") (pin "1") (pinfunction "1_1") (pintype "passive"))
      (node (ref "C13") (pin "2") (pinfunction "2_2") (pintype "passive"))
      (node (ref "C14") (pin "2") (pinfunction "2_2") (pintype "passive"))
      (node (ref "C15") (pin "2") (pinfunction "2_2") (pintype "passive"))
      (node (ref "C17") (pin "1") (pinfunction "1_1") (pintype "passive"))
      (node (ref "C18") (pin "1") (pinfunction "1_1") (pintype "passive"))
      (node (ref "C19") (pin "1") (pinfunction "1_1") (pintype "passive"))
      (node (ref "C2") (pin "2") (pinfunction "2_2") (pintype "passive"))
      (node (ref "C20") (pin "2") (pinfunction "2_2") (pintype "passive"))
      (node (ref "C21") (pin "2") (pinfunction "2_2") (pintype "passive"))
      (node (ref "C22") (pin "2") (pinfunction "2_2") (pintype "passive"))
      (node (ref "C23") (pin "2") (pinfunction "2_2") (pintype "passive"))
      (node (ref "C24") (pin "2") (pinfunction "2_2") (pintype "passive"))
      (node (ref "C25") (pin "1") (pinfunction "1_1") (pintype "passive"))
      (node (ref "C26") (pin "1") (pinfunction "1_1") (pintype "passive"))
      (node (ref "C3") (pin "2") (pinfunction "2_2") (pintype "passive"))
      (node (ref "C30") (pin "2") (pinfunction "2_2") (pintype "passive"))
      (node (ref "C31") (pin "2") (pinfunction "2_2") (pintype "passive"))
      (node (ref "C32") (pin "2") (pinfunction "2_2") (pintype "passive"))
      (node (ref "C33") (pin "1") (pinfunction "1_1") (pintype "passive"))
      (node (ref "C34") (pin "2") (pinfunction "2_2") (pintype "passive"))
      (node (ref "C35") (pin "2") (pinfunction "2_2") (pintype "passive"))
      (node (ref "C36") (pin "2") (pinfunction "2_2") (pintype "passive"))
      (node (ref "C37") (pin "2") (pinfunction "2_2") (pintype "passive"))
      (node (ref "C38") (pin "2") (pinfunction "2_2") (pintype "passive"))
      (node (ref "C39") (pin "2") (pinfunction "2_2") (pintype "passive"))
      (node (ref "C4") (pin "2") (pinfunction "2_2") (pintype "passive"))
      (node (ref "C40") (pin "2") (pinfunction "2_2") (pintype "passive"))
      (node (ref "C42") (pin "1") (pinfunction "1_1") (pintype "passive"))
      (node (ref "C43") (pin "2") (pinfunction "2_2") (pintype "passive"))
      (node (ref "C45") (pin "2") (pinfunction "2_2") (pintype "passive"))
      (node (ref "C46") (pin "2") (pinfunction "2_2") (pintype "passive"))
      (node (ref "C48") (pin "2") (pinfunction "2_2") (pintype "passive"))
      (node (ref "C49") (pin "2") (pinfunction "2_2") (pintype "passive"))
      (node (ref "C5") (pin "2") (pinfunction "2_2") (pintype "passive"))
      (node (ref "C50") (pin "2") (pinfunction "2_2") (pintype "passive"))
      (node (ref "C51") (pin "1") (pinfunction "1_1") (pintype "passive"))
      (node (ref "C52") (pin "1") (pinfunction "1_1") (pintype "passive"))
      (node (ref "C54") (pin "2") (pinfunction "2_2") (pintype "passive"))
      (node (ref "C6") (pin "2") (pinfunction "2_2") (pintype "passive"))
      (node (ref "C7") (pin "2") (pinfunction "2_2") (pintype "passive"))
      (node (ref "C8") (pin "2") (pinfunction "2_2") (pintype "passive"))
      (node (ref "J1") (pin "2") (pinfunction "GND_2") (pintype "power_in"))
      (node (ref "J1") (pin "3") (pinfunction "GND_3") (pintype "power_in"))
      (node (ref "J2") (pin "2") (pinfunction "GND_2") (pintype "power_in"))
      (node (ref "J2") (pin "3") (pinfunction "GND_3") (pintype "power_in"))
      (node (ref "J3") (pin "2") (pinfunction "GND_2") (pintype "power_in"))
      (node (ref "J3") (pin "3") (pinfunction "GND_3") (pintype "power_in"))
      (node (ref "J4") (pin "1") (pinfunction "MNT_1_1") (pintype "passive"))
      (node (ref "J4") (pin "2") (pinfunction "MNT_2_2") (pintype "passive"))
      (node (ref "J4") (pin "3") (pinfunction "MNT_3_3") (pintype "passive"))
      (node (ref "J4") (pin "4") (pinfunction "MNT_4_4") (pintype "passive"))
      (node (ref "J4") (pin "A1") (pinfunction "GND_A1") (pintype "power_in"))
      (node (ref "J4") (pin "A12") (pinfunction "GND_A12") (pintype "power_in"))
      (node (ref "J4") (pin "B1") (pinfunction "GND_B1") (pintype "power_in"))
      (node (ref "J4") (pin "B12") (pinfunction "GND_B12") (pintype "power_in"))
      (node (ref "J5") (pin "2") (pinfunction "GND_2") (pintype "power_in"))
      (node (ref "J5") (pin "3") (pinfunction "GND_3") (pintype "power_in"))
      (node (ref "J6") (pin "2") (pinfunction "GND_2") (pintype "power_in"))
      (node (ref "J6") (pin "3") (pinfunction "GND_3") (pintype "power_in"))
      (node (ref "J7") (pin "3") (pinfunction "3_3") (pintype "passive"))
      (node (ref "J8") (pin "3") (pinfunction "3_3") (pintype "passive"))
      (node (ref "J9") (pin "3") (pinfunction "3_3") (pintype "passive"))
      (node (ref "P3") (pin "2") (pinfunction "Y_2") (pintype "passive"))
      (node (ref "P4") (pin "1") (pinfunction "1_1") (pintype "passive"))
      (node (ref "P4") (pin "2") (pinfunction "2_2") (pintype "passive"))
      (node (ref "P4") (pin "3") (pinfunction "3_3") (pintype "passive"))
      (node (ref "P4") (pin "4") (pinfunction "4_4") (pintype "passive"))
      (node (ref "P4") (pin "5") (pinfunction "5_5") (pintype "passive"))
      (node (ref "P4") (pin "6") (pinfunction "6_6") (pintype "passive"))
      (node (ref "P4") (pin "7") (pinfunction "7_7") (pintype "passive"))
      (node (ref "P4") (pin "8") (pinfunction "8_8") (pintype "passive"))
      (node (ref "R4") (pin "1") (pinfunction "1_1") (pintype "passive"))
      (node (ref "R40") (pin "1") (pinfunction "1_1") (pintype "passive"))
      (node (ref "R42") (pin "1") (pinfunction "1_1") (pintype "passive"))
      (node (ref "R43") (pin "2") (pinfunction "2_2") (pintype "passive"))
      (node (ref "R44") (pin "1") (pinfunction "1_1") (pintype "passive"))
      (node (ref "R46") (pin "1") (pinfunction "1_1") (pintype "passive"))
      (node (ref "R5") (pin "1") (pinfunction "1_1") (pintype "passive"))
      (node (ref "U10") (pin "14") (pinfunction "MODE_14") (pintype "input"))
      (node (ref "U10") (pin "17") (pinfunction "EP_17") (pintype "power_in"))
      (node (ref "U2") (pin "2") (pinfunction "GND_2") (pintype "power_in"))
      (node (ref "U3") (pin "2") (pinfunction "GND_2") (pintype "power_in"))
      (node (ref "U4") (pin "25") (pinfunction "GND_25") (pintype "passive"))
      (node (ref "U5") (pin "1") (pinfunction "T/~{R}_1") (pintype "passive"))
      (node (ref "U5") (pin "10") (pinfunction "GND_10") (pintype "passive"))
      (node (ref "U5") (pin "19") (pinfunction "~{OE}_19") (pintype "passive"))
      (node (ref "U6") (pin "11") (pinfunction "GND_11") (pintype "power_in"))
      (node (ref "U6") (pin "15") (pinfunction "GND_15") (pintype "power_in"))
      (node (ref "U6") (pin "16") (pinfunction "SHDN_16") (pintype "input"))
      (node (ref "U6") (pin "23") (pinfunction "OGND_23") (pintype "power_in"))
      (node (ref "U6") (pin "31") (pinfunction "OGND_31") (pintype "power_in"))
      (node (ref "U6") (pin "38") (pinfunction "OGND_38") (pintype "power_in"))
      (node (ref "U6") (pin "44") (pinfunction "~{OE}_44") (pintype "output"))
      (node (ref "U6") (pin "47") (pinfunction "PGA_47") (pintype "input"))
      (node (ref "U6") (pin "48") (pinfunction "GND_48") (pintype "power_in"))
      (node (ref "U6") (pin "49") (pinfunction "EP_49") (pintype "power_in"))
      (node (ref "U6") (pin "5") (pinfunction "GND_5") (pintype "power_in"))
      (node (ref "U6") (pin "8") (pinfunction "GND_8") (pintype "power_in"))
      (node (ref "U6") (pin "9") (pinfunction "GND_9") (pintype "power_in"))
      (node (ref "U7") (pin "1") (pinfunction "-IN_1") (pintype "tri_state"))
      (node (ref "U7") (pin "6") (pinfunction "V-_6") (pintype "power_in"))
      (node (ref "U8") (pin "1") (pinfunction "T/~{R}_1") (pintype "passive"))
      (node (ref "U8") (pin "10") (pinfunction "GND_10") (pintype "passive"))
      (node (ref "U8") (pin "19") (pinfunction "~{OE}_19") (pintype "passive"))
    )
    (net (code "21") (name "Net-(C30-Pad1)") (class "Default")
      (node (ref "C30") (pin "1") (pinfunction "1_1") (pintype "passive"))
      (node (ref "R9") (pin "2") (pinfunction "2_2") (pintype "passive"))
    )
    (net (code "22") (name "Net-(C31-Pad1)") (class "Default")
      (node (ref "C31") (pin "1") (pinfunction "1_1") (pintype "passive"))
      (node (ref "R10") (pin "2") (pinfunction "2_2") (pintype "passive"))
    )
    (net (code "23") (name "Net-(C32-Pad1)") (class "Default")
      (node (ref "C32") (pin "1") (pinfunction "1_1") (pintype "passive"))
      (node (ref "R11") (pin "2") (pinfunction "2_2") (pintype "passive"))
    )
    (net (code "24") (name "Net-(C42-Pad2)") (class "Default")
      (node (ref "C42") (pin "2") (pinfunction "2_2") (pintype "passive"))
      (node (ref "C44") (pin "1") (pinfunction "1_1") (pintype "passive"))
      (node (ref "R26") (pin "1") (pinfunction "1_1") (pintype "passive"))
      (node (ref "R28") (pin "1") (pinfunction "1_1") (pintype "passive"))
    )
    (net (code "25") (name "Net-(C44-Pad2)") (class "Default")
      (node (ref "C44") (pin "2") (pinfunction "2_2") (pintype "passive"))
      (node (ref "C46") (pin "1") (pinfunction "1_1") (pintype "passive"))
      (node (ref "R30") (pin "1") (pinfunction "1_1") (pintype "passive"))
      (node (ref "R33") (pin "1") (pinfunction "1_1") (pintype "passive"))
    )
    (net (code "26") (name "Net-(J1-SIG)") (class "Default")
      (node (ref "C9") (pin "1") (pinfunction "1_1") (pintype "passive"))
      (node (ref "J1") (pin "1") (pinfunction "SIG_1") (pintype "input"))
    )
    (net (code "27") (name "Net-(J2-SIG)") (class "Default")
      (node (ref "C10") (pin "1") (pinfunction "1_1") (pintype "passive"))
      (node (ref "J2") (pin "1") (pinfunction "SIG_1") (pintype "input"))
    )
    (net (code "28") (name "Net-(J3-SIG)") (class "Default")
      (node (ref "C11") (pin "1") (pinfunction "1_1") (pintype "passive"))
      (node (ref "J3") (pin "1") (pinfunction "SIG_1") (pintype "input"))
    )
    (net (code "29") (name "Net-(J5-SIG)") (class "Default")
      (node (ref "C41") (pin "1") (pinfunction "1_1") (pintype "passive"))
      (node (ref "J5") (pin "1") (pinfunction "SIG_1") (pintype "input"))
    )
    (net (code "30") (name "Net-(J6-SIG)") (class "Default")
      (node (ref "C47") (pin "2") (pinfunction "2_2") (pintype "passive"))
      (node (ref "J6") (pin "1") (pinfunction "SIG_1") (pintype "input"))
    )
    (net (code "31") (name "Net-(J8-Pad1)") (class "Default")
      (node (ref "J8") (pin "1") (pinfunction "1_1") (pintype "passive"))
      (node (ref "R37") (pin "1") (pinfunction "1_1") (pintype "passive"))
    )
    (net (code "32") (name "Net-(J9-Pad1)") (class "Default")
      (node (ref "J9") (pin "1") (pinfunction "1_1") (pintype "passive"))
      (node (ref "R38") (pin "1") (pinfunction "1_1") (pintype "passive"))
    )
    (net (code "33") (name "Net-(P3-X)") (class "Default")
      (node (ref "C16") (pin "1") (pinfunction "1_1") (pintype "passive"))
      (node (ref "P3") (pin "1") (pinfunction "X_1") (pintype "passive"))
      (node (ref "R4") (pin "2") (pinfunction "2_2") (pintype "passive"))
    )
    (net (code "34") (name "Net-(U1B-+IN2)") (class "Default")
      (node (ref "C16") (pin "2") (pinfunction "2_2") (pintype "passive"))
      (node (ref "R46") (pin "2") (pinfunction "2_2") (pintype "passive"))
      (node (ref "U1") (pin "5") (pinfunction "+IN2_5") (pintype "tri_state"))
    )
    (net (code "35") (name "Net-(U1B--IN2)") (class "Default")
      (node (ref "C27") (pin "1") (pinfunction "1_1") (pintype "passive"))
      (node (ref "R6") (pin "1") (pinfunction "1_1") (pintype "passive"))
      (node (ref "R9") (pin "1") (pinfunction "1_1") (pintype "passive"))
      (node (ref "U1") (pin "6") (pinfunction "-IN2_6") (pintype "tri_state"))
    )
    (net (code "36") (name "Net-(U1B-VOUT2)") (class "Default")
      (node (ref "C27") (pin "2") (pinfunction "2_2") (pintype "passive"))
      (node (ref "C9") (pin "2") (pinfunction "2_2") (pintype "passive"))
      (node (ref "R1") (pin "1") (pinfunction "1_1") (pintype "passive"))
      (node (ref "R6") (pin "2") (pinfunction "2_2") (pintype "passive"))
      (node (ref "U1") (pin "7") (pinfunction "VOUT2_7") (pintype "passive"))
    )
    (net (code "37") (name "Net-(U1C-+IN3)") (class "Default")
      (node (ref "R1") (pin "2") (pinfunction "2_2") (pintype "passive"))
      (node (ref "U1") (pin "10") (pinfunction "+IN3_10") (pintype "tri_state"))
    )
    (net (code "38") (name "Net-(U1C--IN3)") (class "Default")
      (node (ref "C28") (pin "1") (pinfunction "1_1") (pintype "passive"))
      (node (ref "R10") (pin "1") (pinfunction "1_1") (pintype "passive"))
      (node (ref "R7") (pin "1") (pinfunction "1_1") (pintype "passive"))
      (node (ref "U1") (pin "9") (pinfunction "-IN3_9") (pintype "tri_state"))
    )
    (net (code "39") (name "Net-(U1C-VOUT3)") (class "Default")
      (node (ref "C10") (pin "2") (pinfunction "2_2") (pintype "passive"))
      (node (ref "C28") (pin "2") (pinfunction "2_2") (pintype "passive"))
      (node (ref "R2") (pin "1") (pinfunction "1_1") (pintype "passive"))
      (node (ref "R7") (pin "2") (pinfunction "2_2") (pintype "passive"))
      (node (ref "U1") (pin "8") (pinfunction "VOUT3_8") (pintype "passive"))
    )
    (net (code "40") (name "Net-(U1D-+IN4)") (class "Default")
      (node (ref "R2") (pin "2") (pinfunction "2_2") (pintype "passive"))
      (node (ref "U1") (pin "12") (pinfunction "+IN4_12") (pintype "tri_state"))
    )
    (net (code "41") (name "Net-(U1D--IN4)") (class "Default")
      (node (ref "C29") (pin "1") (pinfunction "1_1") (pintype "passive"))
      (node (ref "R11") (pin "1") (pinfunction "1_1") (pintype "passive"))
      (node (ref "R8") (pin "1") (pinfunction "1_1") (pintype "passive"))
      (node (ref "U1") (pin "13") (pinfunction "-IN4_13") (pintype "tri_state"))
    )
    (net (code "42") (name "Net-(U1D-VOUT4)") (class "Default")
      (node (ref "C11") (pin "2") (pinfunction "2_2") (pintype "passive"))
      (node (ref "C29") (pin "2") (pinfunction "2_2") (pintype "passive"))
      (node (ref "R3") (pin "1") (pinfunction "1_1") (pintype "passive"))
      (node (ref "R5") (pin "2") (pinfunction "2_2") (pintype "passive"))
      (node (ref "R8") (pin "2") (pinfunction "2_2") (pintype "passive"))
      (node (ref "U1") (pin "14") (pinfunction "VOUT4_14") (pintype "passive"))
    )
    (net (code "43") (name "Net-(U2-VOUT)") (class "Default")
      (node (ref "C18") (pin "2") (pinfunction "2_2") (pintype "passive"))
      (node (ref "U2") (pin "5") (pinfunction "VOUT_5") (pintype "passive"))
      (node (ref "W3") (pin "1") (pinfunction "C1_1") (pintype "passive"))
    )
    (net (code "44") (name "Net-(U3-VOUT)") (class "Default")
      (node (ref "C26") (pin "2") (pinfunction "2_2") (pintype "passive"))
      (node (ref "U3") (pin "5") (pinfunction "VOUT_5") (pintype "power_in"))
      (node (ref "W4") (pin "1") (pinfunction "C1_1") (pintype "passive"))
    )
    (net (code "45") (name "Net-(U4-A15)") (class "Default")
      (node (ref "R20") (pin "2") (pinfunction "2_2") (pintype "passive"))
      (node (ref "U4") (pin "15") (pinfunction "A15_15") (pintype "passive"))
    )
    (net (code "46") (name "Net-(U4-A16)") (class "Default")
      (node (ref "R21") (pin "2") (pinfunction "2_2") (pintype "passive"))
      (node (ref "U4") (pin "16") (pinfunction "A16_16") (pintype "passive"))
    )
    (net (code "47") (name "Net-(U4-D7)") (class "Default")
      (node (ref "R12") (pin "2") (pinfunction "2_2") (pintype "passive"))
      (node (ref "U4") (pin "7") (pinfunction "D7_7") (pintype "passive"))
    )
    (net (code "48") (name "Net-(U4-D8)") (class "Default")
      (node (ref "R13") (pin "2") (pinfunction "2_2") (pintype "passive"))
      (node (ref "U4") (pin "8") (pinfunction "D8_8") (pintype "passive"))
    )
    (net (code "49") (name "Net-(U4-D9)") (class "Default")
      (node (ref "R14") (pin "2") (pinfunction "2_2") (pintype "passive"))
      (node (ref "U4") (pin "9") (pinfunction "D9_9") (pintype "passive"))
    )
    (net (code "50") (name "Net-(U4-D10)") (class "Default")
      (node (ref "R15") (pin "2") (pinfunction "2_2") (pintype "passive"))
      (node (ref "U4") (pin "10") (pinfunction "D10_10") (pintype "passive"))
    )
    (net (code "51") (name "Net-(U4-D11)") (class "Default")
      (node (ref "R16") (pin "2") (pinfunction "2_2") (pintype "passive"))
      (node (ref "U4") (pin "11") (pinfunction "D11_11") (pintype "passive"))
    )
    (net (code "52") (name "Net-(U4-D12)") (class "Default")
      (node (ref "R17") (pin "2") (pinfunction "2_2") (pintype "passive"))
      (node (ref "U4") (pin "12") (pinfunction "D12_12") (pintype "passive"))
    )
    (net (code "53") (name "Net-(U4-D13)") (class "Default")
      (node (ref "R18") (pin "2") (pinfunction "2_2") (pintype "passive"))
      (node (ref "U4") (pin "13") (pinfunction "D13_13") (pintype "passive"))
    )
    (net (code "54") (name "Net-(U4-D14)") (class "Default")
      (node (ref "R19") (pin "2") (pinfunction "2_2") (pintype "passive"))
      (node (ref "U4") (pin "14") (pinfunction "D14_14") (pintype "passive"))
    )
    (net (code "55") (name "Net-(U4-D17)") (class "Default")
      (node (ref "R23") (pin "2") (pinfunction "2_2") (pintype "passive"))
      (node (ref "U4") (pin "17") (pinfunction "D17_17") (pintype "passive"))
    )
    (net (code "56") (name "Net-(U4-D18)") (class "Default")
      (node (ref "R24") (pin "2") (pinfunction "2_2") (pintype "passive"))
      (node (ref "U4") (pin "18") (pinfunction "D18_18") (pintype "passive"))
    )
    (net (code "57") (name "Net-(U4-D19)") (class "Default")
      (node (ref "R27") (pin "2") (pinfunction "2_2") (pintype "passive"))
      (node (ref "U4") (pin "19") (pinfunction "D19_19") (pintype "passive"))
    )
    (net (code "58") (name "Net-(U4-D20)") (class "Default")
      (node (ref "R29") (pin "2") (pinfunction "2_2") (pintype "passive"))
      (node (ref "U4") (pin "20") (pinfunction "D20_20") (pintype "passive"))
    )
    (net (code "59") (name "Net-(U4-D21)") (class "Default")
      (node (ref "R31") (pin "2") (pinfunction "2_2") (pintype "passive"))
      (node (ref "U4") (pin "21") (pinfunction "D21_21") (pintype "passive"))
    )
    (net (code "60") (name "Net-(U4-D22)") (class "Default")
      (node (ref "R32") (pin "2") (pinfunction "2_2") (pintype "passive"))
      (node (ref "U4") (pin "22") (pinfunction "D22_22") (pintype "passive"))
    )
    (net (code "61") (name "Net-(U4-D23)") (class "Default")
      (node (ref "R35") (pin "2") (pinfunction "2_2") (pintype "passive"))
      (node (ref "U4") (pin "23") (pinfunction "D23_23") (pintype "passive"))
    )
    (net (code "62") (name "Net-(U5C-A_0)") (class "Default")
      (node (ref "R20") (pin "1") (pinfunction "1_1") (pintype "passive"))
      (node (ref "U5") (pin "2") (pinfunction "A_0_2") (pintype "passive"))
    )
    (net (code "63") (name "Net-(U5C-A_1)") (class "Default")
      (node (ref "R19") (pin "1") (pinfunction "1_1") (pintype "passive"))
      (node (ref "U5") (pin "3") (pinfunction "A_1_3") (pintype "passive"))
    )
    (net (code "64") (name "Net-(U5C-A_2)") (class "Default")
      (node (ref "R18") (pin "1") (pinfunction "1_1") (pintype "passive"))
      (node (ref "U5") (pin "4") (pinfunction "A_2_4") (pintype "passive"))
    )
    (net (code "65") (name "Net-(U5C-A_3)") (class "Default")
      (node (ref "R17") (pin "1") (pinfunction "1_1") (pintype "passive"))
      (node (ref "U5") (pin "5") (pinfunction "A_3_5") (pintype "passive"))
    )
    (net (code "66") (name "Net-(U5C-A_4)") (class "Default")
      (node (ref "R16") (pin "1") (pinfunction "1_1") (pintype "passive"))
      (node (ref "U5") (pin "6") (pinfunction "A_4_6") (pintype "passive"))
    )
    (net (code "67") (name "Net-(U5C-A_5)") (class "Default")
      (node (ref "R15") (pin "1") (pinfunction "1_1") (pintype "passive"))
      (node (ref "U5") (pin "7") (pinfunction "A_5_7") (pintype "passive"))
    )
    (net (code "68") (name "Net-(U5C-A_6)") (class "Default")
      (node (ref "R14") (pin "1") (pinfunction "1_1") (pintype "passive"))
      (node (ref "U5") (pin "8") (pinfunction "A_6_8") (pintype "passive"))
    )
    (net (code "69") (name "Net-(U5C-A_7)") (class "Default")
      (node (ref "R13") (pin "1") (pinfunction "1_1") (pintype "passive"))
      (node (ref "U5") (pin "9") (pinfunction "A_7_9") (pintype "passive"))
    )
    (net (code "70") (name "Net-(U5C-B_0)") (class "Default")
      (node (ref "U5") (pin "18") (pinfunction "B_0_18") (pintype "passive"))
      (node (ref "U6") (pin "32") (pinfunction "D8_32") (pintype "output"))
    )
    (net (code "71") (name "Net-(U5C-B_1)") (class "Default")
      (node (ref "U5") (pin "17") (pinfunction "B_1_17") (pintype "passive"))
      (node (ref "U6") (pin "33") (pinfunction "D9_33") (pintype "output"))
    )
    (net (code "72") (name "Net-(U5C-B_2)") (class "Default")
      (node (ref "U5") (pin "16") (pinfunction "B_2_16") (pintype "passive"))
      (node (ref "U6") (pin "34") (pinfunction "D10_34") (pintype "output"))
    )
    (net (code "73") (name "Net-(U5C-B_3)") (class "Default")
      (node (ref "U5") (pin "15") (pinfunction "B_3_15") (pintype "passive"))
      (node (ref "U6") (pin "35") (pinfunction "D11_35") (pintype "output"))
    )
    (net (code "74") (name "Net-(U5C-B_4)") (class "Default")
      (node (ref "U5") (pin "14") (pinfunction "B_4_14") (pintype "passive"))
      (node (ref "U6") (pin "39") (pinfunction "D12_39") (pintype "output"))
    )
    (net (code "75") (name "Net-(U5C-B_5)") (class "Default")
      (node (ref "U5") (pin "13") (pinfunction "B_5_13") (pintype "passive"))
      (node (ref "U6") (pin "40") (pinfunction "D13_40") (pintype "output"))
    )
    (net (code "76") (name "Net-(U5C-B_6)") (class "Default")
      (node (ref "U5") (pin "12") (pinfunction "B_6_12") (pintype "passive"))
      (node (ref "U6") (pin "41") (pinfunction "D14_41") (pintype "output"))
    )
    (net (code "77") (name "Net-(U5C-B_7)") (class "Default")
      (node (ref "U5") (pin "11") (pinfunction "B_7_11") (pintype "passive"))
      (node (ref "U6") (pin "42") (pinfunction "D15_42") (pintype "output"))
    )
    (net (code "78") (name "Net-(U6-AIN+)") (class "Default")
      (node (ref "R26") (pin "2") (pinfunction "2_2") (pintype "passive"))
      (node (ref "U6") (pin "6") (pinfunction "AIN+_6") (pintype "passive"))
    )
    (net (code "79") (name "Net-(U6-AIN-)") (class "Default")
      (node (ref "R30") (pin "2") (pinfunction "2_2") (pintype "passive"))
      (node (ref "U6") (pin "7") (pinfunction "AIN-_7") (pintype "passive"))
    )
    (net (code "80") (name "Net-(U6-CLK)") (class "Default")
      (node (ref "R34") (pin "2") (pinfunction "2_2") (pintype "passive"))
      (node (ref "U6") (pin "10") (pinfunction "CLK_10") (pintype "passive"))
    )
    (net (code "81") (name "Net-(U6-D0)") (class "Default")
      (node (ref "U6") (pin "18") (pinfunction "D0_18") (pintype "output"))
      (node (ref "U8") (pin "18") (pinfunction "B_0_18") (pintype "passive"))
    )
    (net (code "82") (name "Net-(U6-D1)") (class "Default")
      (node (ref "U6") (pin "19") (pinfunction "D1_19") (pintype "output"))
      (node (ref "U8") (pin "17") (pinfunction "B_1_17") (pintype "passive"))
    )
    (net (code "83") (name "Net-(U6-D2)") (class "Default")
      (node (ref "U6") (pin "20") (pinfunction "D2_20") (pintype "output"))
      (node (ref "U8") (pin "16") (pinfunction "B_2_16") (pintype "passive"))
    )
    (net (code "84") (name "Net-(U6-D3)") (class "Default")
      (node (ref "U6") (pin "21") (pinfunction "D3_21") (pintype "output"))
      (node (ref "U8") (pin "15") (pinfunction "B_3_15") (pintype "passive"))
    )
    (net (code "85") (name "Net-(U6-D4)") (class "Default")
      (node (ref "U6") (pin "22") (pinfunction "D4_22") (pintype "output"))
      (node (ref "U8") (pin "14") (pinfunction "B_4_14") (pintype "passive"))
    )
    (net (code "86") (name "Net-(U6-D5)") (class "Default")
      (node (ref "U6") (pin "26") (pinfunction "D5_26") (pintype "output"))
      (node (ref "U8") (pin "13") (pinfunction "B_5_13") (pintype "passive"))
    )
    (net (code "87") (name "Net-(U6-D6)") (class "Default")
      (node (ref "U6") (pin "27") (pinfunction "D6_27") (pintype "output"))
      (node (ref "U8") (pin "12") (pinfunction "B_6_12") (pintype "passive"))
    )
    (net (code "88") (name "Net-(U6-D7)") (class "Default")
      (node (ref "U6") (pin "28") (pinfunction "D7_28") (pintype "output"))
      (node (ref "U8") (pin "11") (pinfunction "B_7_11") (pintype "passive"))
    )
    (net (code "89") (name "Net-(U6-SENSE)") (class "Default")
      (node (ref "R36") (pin "1") (pinfunction "1_1") (pintype "passive"))
      (node (ref "U6") (pin "1") (pinfunction "SENSE_1") (pintype "passive"))
    )
    (net (code "90") (name "Net-(U7-+IN)") (class "Default")
      (node (ref "R25") (pin "2") (pinfunction "2_2") (pintype "passive"))
      (node (ref "U7") (pin "8") (pinfunction "+IN_8") (pintype "tri_state"))
    )
    (net (code "91") (name "Net-(U7-+OUT)") (class "Default")
      (node (ref "C41") (pin "2") (pinfunction "2_2") (pintype "passive"))
      (node (ref "R28") (pin "2") (pinfunction "2_2") (pintype "passive"))
      (node (ref "U7") (pin "4") (pinfunction "+OUT_4") (pintype "passive"))
    )
    (net (code "92") (name "Net-(U7--OUT)") (class "Default")
      (node (ref "C47") (pin "1") (pinfunction "1_1") (pintype "passive"))
      (node (ref "R33") (pin "2") (pinfunction "2_2") (pintype "passive"))
      (node (ref "U7") (pin "5") (pinfunction "-OUT_5") (pintype "passive"))
    )
    (net (code "93") (name "Net-(U7-VOCM)") (class "Default")
      (node (ref "R22") (pin "2") (pinfunction "2_2") (pintype "passive"))
      (node (ref "U7") (pin "2") (pinfunction "VOCM_2") (pintype "passive"))
    )
    (net (code "94") (name "Net-(U8C-A_0)") (class "Default")
      (node (ref "R35") (pin "1") (pinfunction "1_1") (pintype "passive"))
      (node (ref "U8") (pin "2") (pinfunction "A_0_2") (pintype "passive"))
    )
    (net (code "95") (name "Net-(U8C-A_1)") (class "Default")
      (node (ref "R32") (pin "1") (pinfunction "1_1") (pintype "passive"))
      (node (ref "U8") (pin "3") (pinfunction "A_1_3") (pintype "passive"))
    )
    (net (code "96") (name "Net-(U8C-A_2)") (class "Default")
      (node (ref "R31") (pin "1") (pinfunction "1_1") (pintype "passive"))
      (node (ref "U8") (pin "4") (pinfunction "A_2_4") (pintype "passive"))
    )
    (net (code "97") (name "Net-(U8C-A_3)") (class "Default")
      (node (ref "R29") (pin "1") (pinfunction "1_1") (pintype "passive"))
      (node (ref "U8") (pin "5") (pinfunction "A_3_5") (pintype "passive"))
    )
    (net (code "98") (name "Net-(U8C-A_4)") (class "Default")
      (node (ref "R27") (pin "1") (pinfunction "1_1") (pintype "passive"))
      (node (ref "U8") (pin "6") (pinfunction "A_4_6") (pintype "passive"))
    )
    (net (code "99") (name "Net-(U8C-A_5)") (class "Default")
      (node (ref "R24") (pin "1") (pinfunction "1_1") (pintype "passive"))
      (node (ref "U8") (pin "7") (pinfunction "A_5_7") (pintype "passive"))
    )
    (net (code "100") (name "Net-(U8C-A_6)") (class "Default")
      (node (ref "R23") (pin "1") (pinfunction "1_1") (pintype "passive"))
      (node (ref "U8") (pin "8") (pinfunction "A_6_8") (pintype "passive"))
    )
    (net (code "101") (name "Net-(U8C-A_7)") (class "Default")
      (node (ref "R21") (pin "1") (pinfunction "1_1") (pintype "passive"))
      (node (ref "U8") (pin "9") (pinfunction "A_7_9") (pintype "passive"))
    )
    (net (code "102") (name "Net-(U9A-A)") (class "Default")
      (node (ref "J7") (pin "2") (pinfunction "2_2") (pintype "passive"))
      (node (ref "U9") (pin "1") (pinfunction "A_1") (pintype "input"))
    )
    (net (code "103") (name "Net-(U10-C+)") (class "Default")
      (node (ref "C53") (pin "1") (pinfunction "1_1") (pintype "passive"))
      (node (ref "U10") (pin "10") (pinfunction "C+_10") (pintype "passive"))
    )
    (net (code "104") (name "Net-(U10-C-)") (class "Default")
      (node (ref "C53") (pin "2") (pinfunction "2_2") (pintype "passive"))
      (node (ref "U10") (pin "7") (pinfunction "C-_7") (pintype "passive"))
    )
    (net (code "105") (name "Net-(U10-RT)") (class "Default")
      (node (ref "R44") (pin "2") (pinfunction "2_2") (pintype "passive"))
      (node (ref "U10") (pin "2") (pinfunction "RT_2") (pintype "passive"))
    )
    (net (code "106") (name "Net-(U10-VOUT)") (class "Default")
      (node (ref "C50") (pin "1") (pinfunction "1_1") (pintype "passive"))
      (node (ref "U10") (pin "6") (pinfunction "VOUT_6") (pintype "power_in"))
    )
    (net (code "107") (name "unconnected-(J4-CC1-PadA5)") (class "Default")
      (node (ref "J4") (pin "A5") (pinfunction "CC1_A5") (pintype "bidirectional+no_connect"))
    )
    (net (code "108") (name "unconnected-(J4-CC2-PadB5)") (class "Default")
      (node (ref "J4") (pin "B5") (pinfunction "CC2_B5") (pintype "bidirectional+no_connect"))
    )
    (net (code "109") (name "unconnected-(J4-Dn1-PadA7)") (class "Default")
      (node (ref "J4") (pin "A7") (pinfunction "Dn1_A7") (pintype "bidirectional+no_connect"))
    )
    (net (code "110") (name "unconnected-(J4-Dn2-PadB7)") (class "Default")
      (node (ref "J4") (pin "B7") (pinfunction "Dn2_B7") (pintype "bidirectional+no_connect"))
    )
    (net (code "111") (name "unconnected-(J4-Dp1-PadA6)") (class "Default")
      (node (ref "J4") (pin "A6") (pinfunction "Dp1_A6") (pintype "bidirectional+no_connect"))
    )
    (net (code "112") (name "unconnected-(J4-Dp2-PadB6)") (class "Default")
      (node (ref "J4") (pin "B6") (pinfunction "Dp2_B6") (pintype "bidirectional+no_connect"))
    )
    (net (code "113") (name "unconnected-(J4-SBU1-PadA8)") (class "Default")
      (node (ref "J4") (pin "A8") (pinfunction "SBU1_A8") (pintype "bidirectional+no_connect"))
    )
    (net (code "114") (name "unconnected-(J4-SBU2-PadB8)") (class "Default")
      (node (ref "J4") (pin "B8") (pinfunction "SBU2_B8") (pintype "bidirectional+no_connect"))
    )
    (net (code "115") (name "unconnected-(U1A-+IN1-Pad3)") (class "Default")
      (node (ref "U1") (pin "3") (pinfunction "+IN1_3") (pintype "tri_state+no_connect"))
    )
    (net (code "116") (name "unconnected-(U1A--IN1-Pad2)") (class "Default")
      (node (ref "U1") (pin "2") (pinfunction "-IN1_2") (pintype "tri_state+no_connect"))
    )
    (net (code "117") (name "unconnected-(U1A-VOUT1-Pad1)") (class "Default")
      (node (ref "U1") (pin "1") (pinfunction "VOUT1_1") (pintype "passive+no_connect"))
    )
    (net (code "118") (name "unconnected-(U2-NC-Pad4)") (class "Default")
      (node (ref "U2") (pin "4") (pinfunction "NC_4") (pintype "passive"))
    )
    (net (code "119") (name "unconnected-(U3-NC-Pad4)") (class "Default")
      (node (ref "U3") (pin "4") (pinfunction "NC_4") (pintype "passive+no_connect"))
    )
    (net (code "120") (name "unconnected-(U4-D1-Pad1)") (class "Default")
      (node (ref "U4") (pin "1") (pinfunction "D1_1") (pintype "passive"))
    )
    (net (code "121") (name "unconnected-(U4-D2-Pad2)") (class "Default")
      (node (ref "U4") (pin "2") (pinfunction "D2_2") (pintype "passive"))
    )
    (net (code "122") (name "unconnected-(U4-D3-Pad3)") (class "Default")
      (node (ref "U4") (pin "3") (pinfunction "D3_3") (pintype "passive"))
    )
    (net (code "123") (name "unconnected-(U4-D4-Pad4)") (class "Default")
      (node (ref "U4") (pin "4") (pinfunction "D4_4") (pintype "passive"))
    )
    (net (code "124") (name "unconnected-(U4-D5-Pad5)") (class "Default")
      (node (ref "U4") (pin "5") (pinfunction "D5_5") (pintype "passive"))
    )
    (net (code "125") (name "unconnected-(U4-D6-Pad6)") (class "Default")
      (node (ref "U4") (pin "6") (pinfunction "D6_6") (pintype "passive"))
    )
    (net (code "126") (name "unconnected-(U4-D26-Pad26)") (class "Default")
      (node (ref "U4") (pin "26") (pinfunction "D26_26") (pintype "passive"))
    )
    (net (code "127") (name "unconnected-(U4-D27-Pad27)") (class "Default")
      (node (ref "U4") (pin "27") (pinfunction "D27_27") (pintype "passive"))
    )
    (net (code "128") (name "unconnected-(U4-D28-Pad28)") (class "Default")
      (node (ref "U4") (pin "28") (pinfunction "D28_28") (pintype "passive"))
    )
    (net (code "129") (name "unconnected-(U4-D30-Pad30)") (class "Default")
      (node (ref "U4") (pin "30") (pinfunction "D30_30") (pintype "passive"))
    )
    (net (code "130") (name "unconnected-(U4-D31-Pad31)") (class "Default")
      (node (ref "U4") (pin "31") (pinfunction "D31_31") (pintype "passive"))
    )
    (net (code "131") (name "unconnected-(U4-D32-Pad32)") (class "Default")
      (node (ref "U4") (pin "32") (pinfunction "D32_32") (pintype "passive"))
    )
    (net (code "132") (name "unconnected-(U4-D33-Pad33)") (class "Default")
      (node (ref "U4") (pin "33") (pinfunction "D33_33") (pintype "passive"))
    )
    (net (code "133") (name "unconnected-(U4-D34-Pad34)") (class "Default")
      (node (ref "U4") (pin "34") (pinfunction "D34_34") (pintype "passive"))
    )
    (net (code "134") (name "unconnected-(U4-D35-Pad35)") (class "Default")
      (node (ref "U4") (pin "35") (pinfunction "D35_35") (pintype "passive"))
    )
    (net (code "135") (name "unconnected-(U4-D36-Pad36)") (class "Default")
      (node (ref "U4") (pin "36") (pinfunction "D36_36") (pintype "passive"))
    )
    (net (code "136") (name "unconnected-(U4-D37-Pad37)") (class "Default")
      (node (ref "U4") (pin "37") (pinfunction "D37_37") (pintype "passive"))
    )
    (net (code "137") (name "unconnected-(U4-D38-Pad38)") (class "Default")
      (node (ref "U4") (pin "38") (pinfunction "D38_38") (pintype "passive"))
    )
    (net (code "138") (name "unconnected-(U4-D39-Pad39)") (class "Default")
      (node (ref "U4") (pin "39") (pinfunction "D39_39") (pintype "passive"))
    )
    (net (code "139") (name "unconnected-(U4-D40-Pad40)") (class "Default")
      (node (ref "U4") (pin "40") (pinfunction "D40_40") (pintype "passive"))
    )
    (net (code "140") (name "unconnected-(U4-D41-Pad41)") (class "Default")
      (node (ref "U4") (pin "41") (pinfunction "D41_41") (pintype "passive"))
    )
    (net (code "141") (name "unconnected-(U4-D42-Pad42)") (class "Default")
      (node (ref "U4") (pin "42") (pinfunction "D42_42") (pintype "passive"))
    )
    (net (code "142") (name "unconnected-(U4-D43-Pad43)") (class "Default")
      (node (ref "U4") (pin "43") (pinfunction "D43_43") (pintype "passive"))
    )
    (net (code "143") (name "unconnected-(U4-D44-Pad44)") (class "Default")
      (node (ref "U4") (pin "44") (pinfunction "D44_44") (pintype "passive"))
    )
    (net (code "144") (name "unconnected-(U4-D45-Pad45)") (class "Default")
      (node (ref "U4") (pin "45") (pinfunction "D45_45") (pintype "passive"))
    )
    (net (code "145") (name "unconnected-(U4-D46-Pad46)") (class "Default")
      (node (ref "U4") (pin "46") (pinfunction "D46_46") (pintype "passive"))
    )
    (net (code "146") (name "unconnected-(U4-D47-Pad47)") (class "Default")
      (node (ref "U4") (pin "47") (pinfunction "D47_47") (pintype "passive"))
    )
    (net (code "147") (name "unconnected-(U4-D48-Pad48)") (class "Default")
      (node (ref "U4") (pin "48") (pinfunction "D48_48") (pintype "passive"))
    )
    (net (code "148") (name "unconnected-(U4-VU-Pad24)") (class "Default")
      (node (ref "U4") (pin "24") (pinfunction "VU_24") (pintype "passive"))
    )
    (net (code "149") (name "unconnected-(U6-CLKOUT--Pad29)") (class "Default")
      (node (ref "U6") (pin "29") (pinfunction "CLKOUT-_29") (pintype "passive+no_connect"))
    )
    (net (code "150") (name "unconnected-(U6-OF-Pad43)") (class "Default")
      (node (ref "U6") (pin "43") (pinfunction "OF_43") (pintype "output+no_connect"))
    )
    (net (code "151") (name "unconnected-(U7-~{SHDN}-Pad7)") (class "Default")
      (node (ref "U7") (pin "7") (pinfunction "~{SHDN}_7") (pintype "input+no_connect"))
    )
    (net (code "152") (name "unconnected-(U10-NC-Pad8)") (class "Default")
      (node (ref "U10") (pin "8") (pinfunction "NC_8") (pintype "passive+no_connect"))
    )
    (net (code "153") (name "unconnected-(U10-NC-Pad9)") (class "Default")
      (node (ref "U10") (pin "9") (pinfunction "NC_9") (pintype "passive+no_connect"))
    )
  )
)
